# M8650D.net
KiCad netlist of a schematic drawn in EAGLE
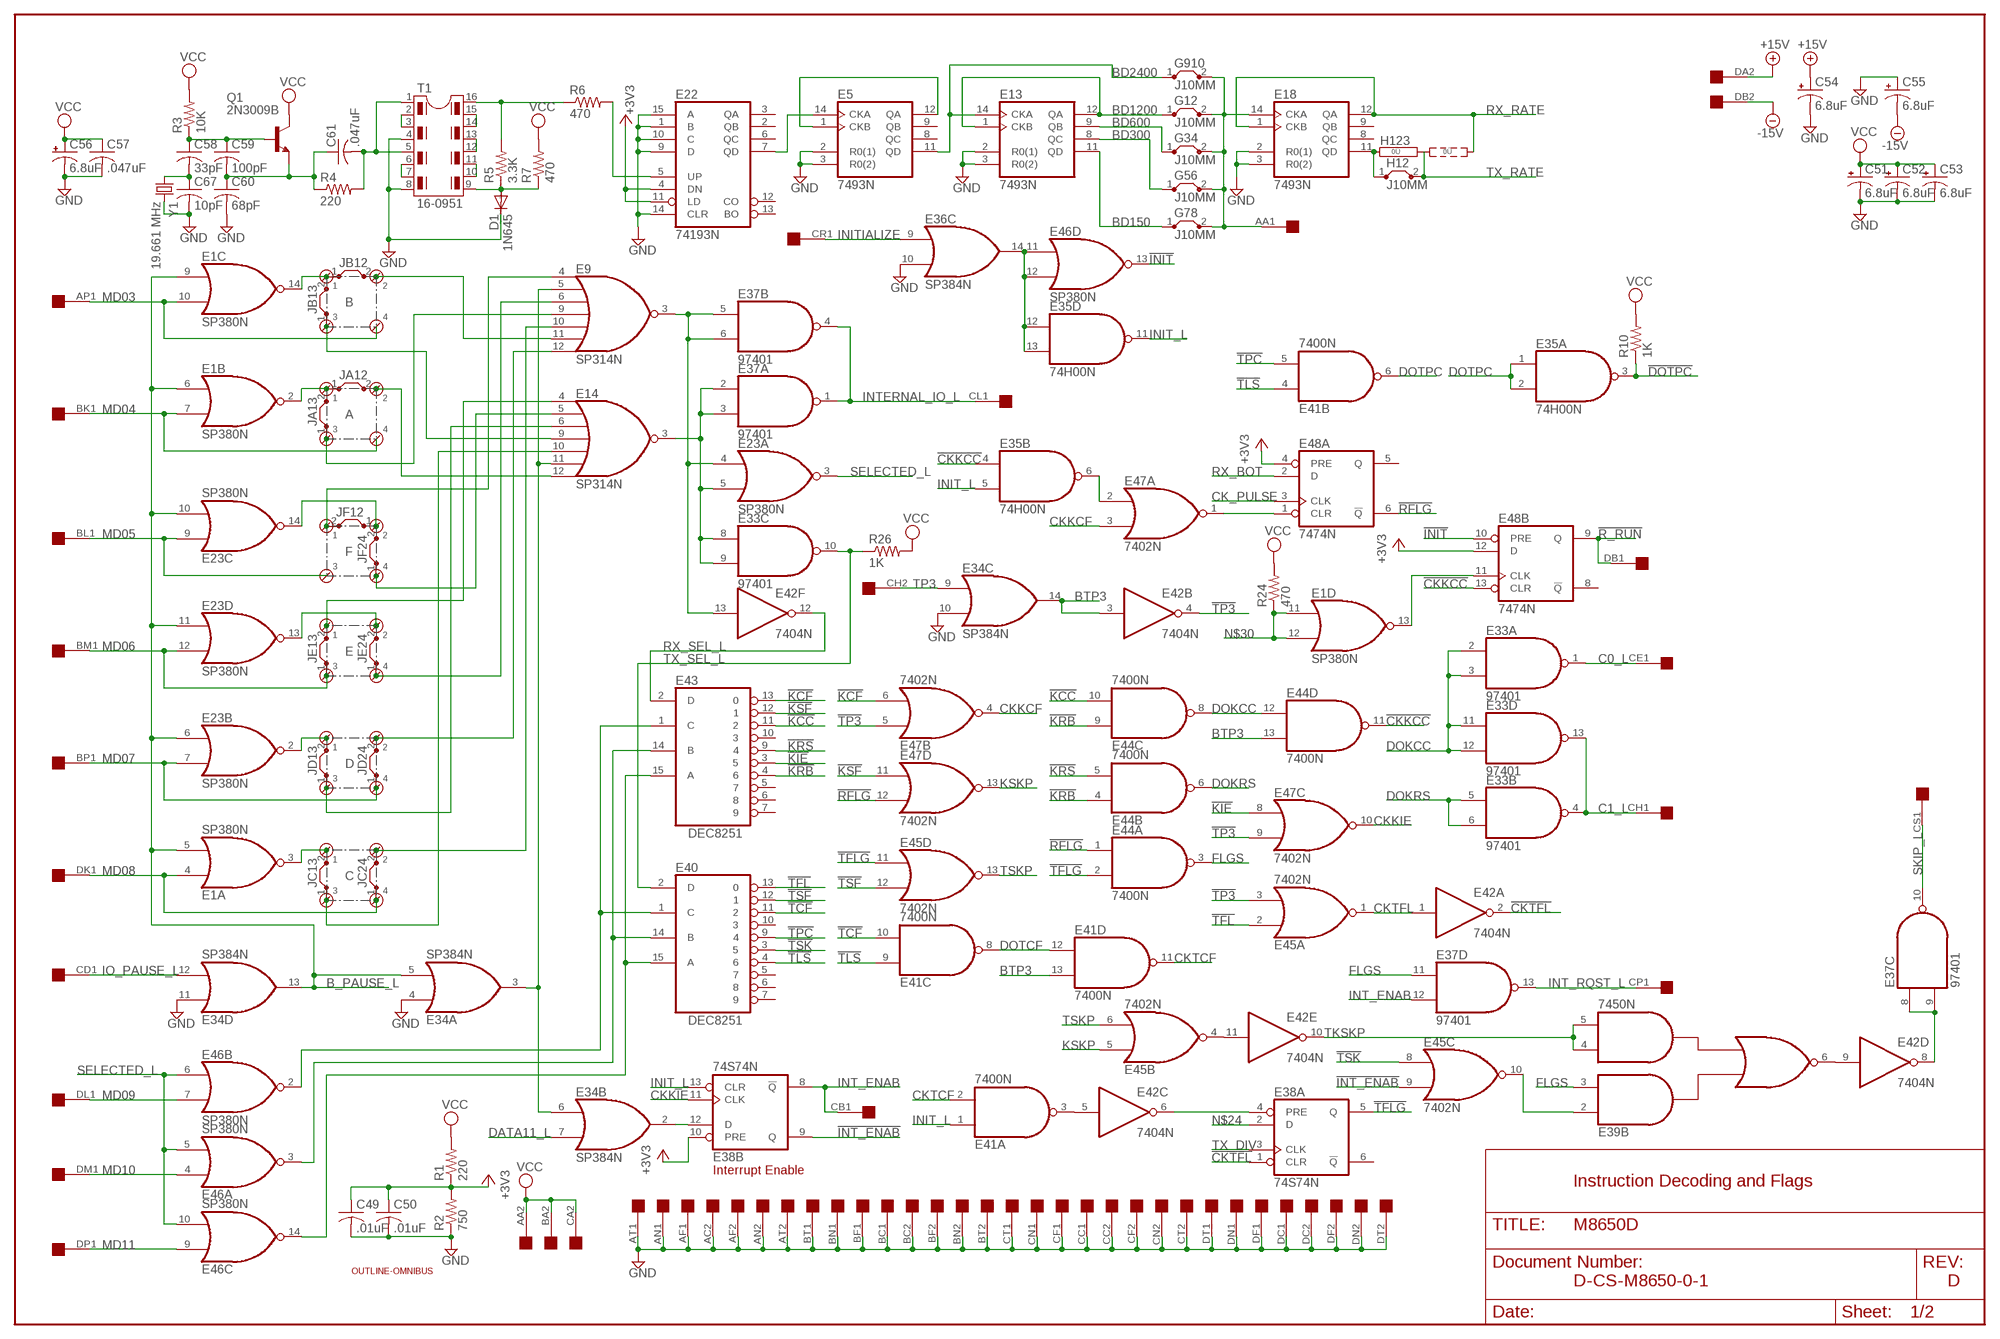
[diagram p0: schematic, sheet 1]
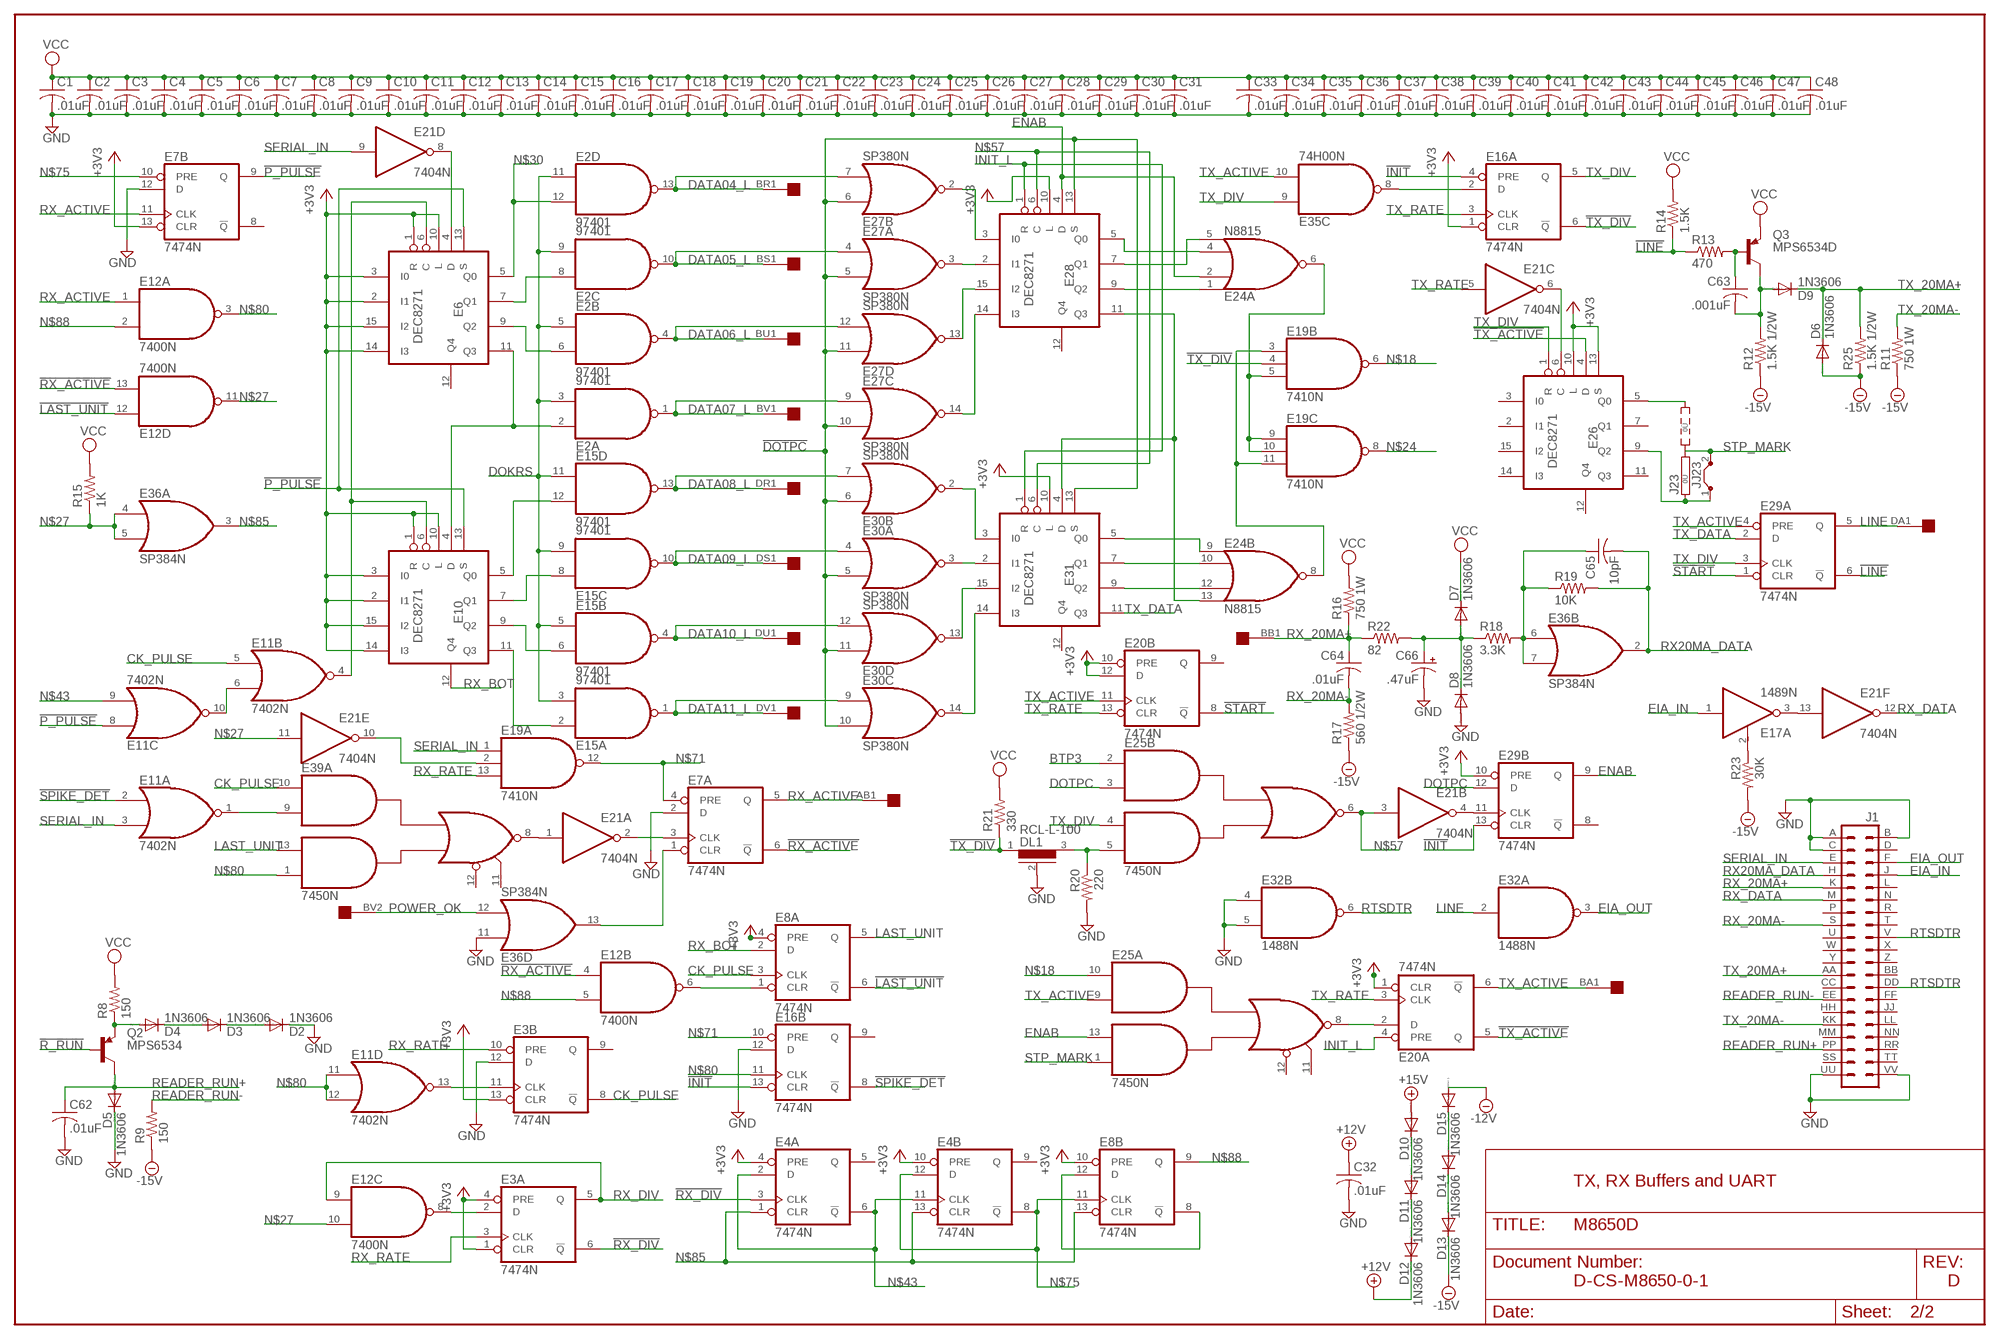
[diagram p1: schematic, sheet 2]

(export (version "E")
  (design (tool "Eeschema 10.0.6"))
  (components
    (comp (ref "A")
      (value "JUMPER4")
      (footprint "eagle-import:JUMPER4")
      (libsource (lib "eagle-import") (part "JUMPER4"))
    )
    (comp (ref "B")
      (value "JUMPER4")
      (footprint "eagle-import:JUMPER4")
      (libsource (lib "eagle-import") (part "JUMPER4"))
    )
    (comp (ref "C")
      (value "JUMPER4")
      (footprint "eagle-import:JUMPER4")
      (libsource (lib "eagle-import") (part "JUMPER4"))
    )
    (comp (ref "C49")
      (value ".01uF")
      (footprint "eagle-import:C050-025X075")
      (libsource (lib "eagle-import") (part "C-US050-025X075"))
    )
    (comp (ref "C50")
      (value ".01uF")
      (footprint "eagle-import:C050-025X075")
      (libsource (lib "eagle-import") (part "C-US050-025X075"))
    )
    (comp (ref "C51")
      (value "6.8uF")
      (footprint "eagle-import:E12-8")
      (libsource (lib "eagle-import") (part "CPOL-USE20-8AXIAL"))
    )
    (comp (ref "C52")
      (value "6.8uF")
      (footprint "eagle-import:E12-8")
      (libsource (lib "eagle-import") (part "CPOL-USE20-8AXIAL"))
    )
    (comp (ref "C53")
      (value "6.8uF")
      (footprint "eagle-import:E12-8")
      (libsource (lib "eagle-import") (part "CPOL-USE20-8AXIAL"))
    )
    (comp (ref "C54")
      (value "6.8uF")
      (footprint "eagle-import:E12-8")
      (libsource (lib "eagle-import") (part "CPOL-USE20-8AXIAL"))
    )
    (comp (ref "C55")
      (value "6.8uF")
      (footprint "eagle-import:E12-8")
      (libsource (lib "eagle-import") (part "CPOL-USE20-8AXIAL"))
    )
    (comp (ref "C56")
      (value "6.8uF")
      (footprint "eagle-import:E12-8")
      (libsource (lib "eagle-import") (part "CPOL-USE20-8AXIAL"))
    )
    (comp (ref "C57")
      (value ".047uF")
      (footprint "eagle-import:C050-025X075")
      (libsource (lib "eagle-import") (part "C-US050-025X075"))
    )
    (comp (ref "C58")
      (value "33pF")
      (footprint "eagle-import:C050-025X075")
      (libsource (lib "eagle-import") (part "C-US050-025X075"))
    )
    (comp (ref "C59")
      (value "100pF")
      (footprint "eagle-import:C050-025X075")
      (libsource (lib "eagle-import") (part "C-US050-025X075"))
    )
    (comp (ref "C60")
      (value "68pF")
      (footprint "eagle-import:C050-025X075")
      (libsource (lib "eagle-import") (part "C-US050-025X075"))
    )
    (comp (ref "C61")
      (value ".047uF")
      (footprint "eagle-import:C050-025X075")
      (libsource (lib "eagle-import") (part "C-US050-025X075"))
    )
    (comp (ref "C67")
      (value "10pF")
      (footprint "eagle-import:C050-025X075")
      (libsource (lib "eagle-import") (part "C-US050-025X075"))
    )
    (comp (ref "D")
      (value "JUMPER4")
      (footprint "eagle-import:JUMPER4")
      (libsource (lib "eagle-import") (part "JUMPER4"))
    )
    (comp (ref "D1")
      (value "1N645")
      (footprint "eagle-import:DO35-10")
      (libsource (lib "eagle-import") (part "DIODE-DO35-10"))
    )
    (comp (ref "E")
      (value "JUMPER4")
      (footprint "eagle-import:JUMPER4")
      (libsource (lib "eagle-import") (part "JUMPER4"))
    )
    (comp (ref "E1")
      (value "SP380N")
      (footprint "eagle-import:DIL14")
      (libsource (lib "eagle-import") (part "SP380N"))
    )
    (comp (ref "E5")
      (value "7493N")
      (footprint "eagle-import:DIL14")
      (libsource (lib "eagle-import") (part "7493NLS"))
    )
    (comp (ref "E9")
      (value "SP314N")
      (footprint "eagle-import:DIL14")
      (libsource (lib "eagle-import") (part "SP314N"))
    )
    (comp (ref "E13")
      (value "7493N")
      (footprint "eagle-import:DIL14")
      (libsource (lib "eagle-import") (part "7493NLS"))
    )
    (comp (ref "E14")
      (value "SP314N")
      (footprint "eagle-import:DIL14")
      (libsource (lib "eagle-import") (part "SP314N"))
    )
    (comp (ref "E18")
      (value "7493N")
      (footprint "eagle-import:DIL14")
      (libsource (lib "eagle-import") (part "7493NLS"))
    )
    (comp (ref "E22")
      (value "74193N")
      (footprint "eagle-import:DIL16")
      (libsource (lib "eagle-import") (part "74193N"))
    )
    (comp (ref "E23")
      (value "SP380N")
      (footprint "eagle-import:DIL14")
      (libsource (lib "eagle-import") (part "SP380N"))
    )
    (comp (ref "E33")
      (value "97401")
      (footprint "eagle-import:DIL14")
      (libsource (lib "eagle-import") (part "7401NLS"))
    )
    (comp (ref "E34")
      (value "SP384N")
      (footprint "eagle-import:DIL14")
      (libsource (lib "eagle-import") (part "SP384N"))
    )
    (comp (ref "E35")
      (value "74H00N")
      (footprint "eagle-import:DIL14")
      (libsource (lib "eagle-import") (part "7400N"))
    )
    (comp (ref "E36")
      (value "SP384N")
      (footprint "eagle-import:DIL14")
      (libsource (lib "eagle-import") (part "SP384N"))
    )
    (comp (ref "E37")
      (value "97401")
      (footprint "eagle-import:DIL14")
      (libsource (lib "eagle-import") (part "7401NLS"))
    )
    (comp (ref "E38")
      (value "74S74N")
      (footprint "eagle-import:DIL14")
      (libsource (lib "eagle-import") (part "7474NS"))
    )
    (comp (ref "E39")
      (value "7450N")
      (footprint "eagle-import:DIL14")
      (libsource (lib "eagle-import") (part "7450N"))
    )
    (comp (ref "E40")
      (value "DEC8251")
      (footprint "eagle-import:DIL16")
      (libsource (lib "eagle-import") (part "DEC8251"))
    )
    (comp (ref "E41")
      (value "7400N")
      (footprint "eagle-import:DIL14")
      (libsource (lib "eagle-import") (part "7400N"))
    )
    (comp (ref "E42")
      (value "7404N")
      (footprint "eagle-import:DIL14")
      (libsource (lib "eagle-import") (part "7404N"))
    )
    (comp (ref "E43")
      (value "DEC8251")
      (footprint "eagle-import:DIL16")
      (libsource (lib "eagle-import") (part "DEC8251"))
    )
    (comp (ref "E44")
      (value "7400N")
      (footprint "eagle-import:DIL14")
      (libsource (lib "eagle-import") (part "7400N"))
    )
    (comp (ref "E45")
      (value "7402N")
      (footprint "eagle-import:DIL14")
      (libsource (lib "eagle-import") (part "7402N"))
    )
    (comp (ref "E46")
      (value "SP380N")
      (footprint "eagle-import:DIL14")
      (libsource (lib "eagle-import") (part "SP380N"))
    )
    (comp (ref "E47")
      (value "7402N")
      (footprint "eagle-import:DIL14")
      (libsource (lib "eagle-import") (part "7402N"))
    )
    (comp (ref "E48")
      (value "7474N")
      (footprint "eagle-import:DIL14")
      (libsource (lib "eagle-import") (part "7474NS"))
    )
    (comp (ref "F")
      (value "JUMPER4")
      (footprint "eagle-import:JUMPER4")
      (libsource (lib "eagle-import") (part "JUMPER4"))
    )
    (comp (ref "G12")
      (value "J10MM")
      (footprint "eagle-import:10")
      (libsource (lib "eagle-import") (part "J10MM"))
    )
    (comp (ref "G34")
      (value "J10MM")
      (footprint "eagle-import:10")
      (libsource (lib "eagle-import") (part "J10MM"))
    )
    (comp (ref "G56")
      (value "J10MM")
      (footprint "eagle-import:10")
      (libsource (lib "eagle-import") (part "J10MM"))
    )
    (comp (ref "G78")
      (value "J10MM")
      (footprint "eagle-import:10")
      (libsource (lib "eagle-import") (part "J10MM"))
    )
    (comp (ref "G910")
      (value "J10MM")
      (footprint "eagle-import:10")
      (libsource (lib "eagle-import") (part "J10MM"))
    )
    (comp (ref "H12")
      (value "J10MM")
      (footprint "eagle-import:10")
      (libsource (lib "eagle-import") (part "J10MM"))
    )
    (comp (ref "H123")
      (value "0R2")
      (footprint "eagle-import:0R2_10")
      (libsource (lib "eagle-import") (part "0R2"))
    )
    (comp (ref "JA12")
      (value "J10MM")
      (footprint "eagle-import:10")
      (libsource (lib "eagle-import") (part "J10MM"))
    )
    (comp (ref "JA13")
      (value "J10MM")
      (footprint "eagle-import:10")
      (libsource (lib "eagle-import") (part "J10MM"))
    )
    (comp (ref "JB12")
      (value "J10MM")
      (footprint "eagle-import:10")
      (libsource (lib "eagle-import") (part "J10MM"))
    )
    (comp (ref "JB13")
      (value "J10MM")
      (footprint "eagle-import:10")
      (libsource (lib "eagle-import") (part "J10MM"))
    )
    (comp (ref "JC13")
      (value "J10MM")
      (footprint "eagle-import:10")
      (libsource (lib "eagle-import") (part "J10MM"))
    )
    (comp (ref "JC24")
      (value "J10MM")
      (footprint "eagle-import:10")
      (libsource (lib "eagle-import") (part "J10MM"))
    )
    (comp (ref "JD13")
      (value "J10MM")
      (footprint "eagle-import:10")
      (libsource (lib "eagle-import") (part "J10MM"))
    )
    (comp (ref "JD24")
      (value "J10MM")
      (footprint "eagle-import:10")
      (libsource (lib "eagle-import") (part "J10MM"))
    )
    (comp (ref "JE13")
      (value "J10MM")
      (footprint "eagle-import:10")
      (libsource (lib "eagle-import") (part "J10MM"))
    )
    (comp (ref "JE24")
      (value "J10MM")
      (footprint "eagle-import:10")
      (libsource (lib "eagle-import") (part "J10MM"))
    )
    (comp (ref "JF12")
      (value "J10MM")
      (footprint "eagle-import:10")
      (libsource (lib "eagle-import") (part "J10MM"))
    )
    (comp (ref "JF24")
      (value "J10MM")
      (footprint "eagle-import:10")
      (libsource (lib "eagle-import") (part "J10MM"))
    )
    (comp (ref "Q1")
      (value "2N3009B")
      (footprint "eagle-import:TO5")
      (libsource (lib "eagle-import") (part "-NPN-TO5"))
    )
    (comp (ref "R1")
      (value "220")
      (footprint "eagle-import:0207_10")
      (libsource (lib "eagle-import") (part "R-US_0207/10"))
    )
    (comp (ref "R2")
      (value "750")
      (footprint "eagle-import:0207_10")
      (libsource (lib "eagle-import") (part "R-US_0207/10"))
    )
    (comp (ref "R3")
      (value "10K")
      (footprint "eagle-import:0207_10")
      (libsource (lib "eagle-import") (part "R-US_0207/10"))
    )
    (comp (ref "R4")
      (value "220")
      (footprint "eagle-import:0207_10")
      (libsource (lib "eagle-import") (part "R-US_0207/10"))
    )
    (comp (ref "R5")
      (value "3.3K")
      (footprint "eagle-import:0207_10")
      (libsource (lib "eagle-import") (part "R-US_0207/10"))
    )
    (comp (ref "R6")
      (value "470")
      (footprint "eagle-import:0207_10")
      (libsource (lib "eagle-import") (part "R-US_0207/10"))
    )
    (comp (ref "R7")
      (value "470")
      (footprint "eagle-import:0207_10")
      (libsource (lib "eagle-import") (part "R-US_0207/10"))
    )
    (comp (ref "R10")
      (value "1K")
      (footprint "eagle-import:0207_10")
      (libsource (lib "eagle-import") (part "R-US_0207/10"))
    )
    (comp (ref "R24")
      (value "470")
      (footprint "eagle-import:0207_10")
      (libsource (lib "eagle-import") (part "R-US_0207/10"))
    )
    (comp (ref "R26")
      (value "1K")
      (footprint "eagle-import:0207_10")
      (libsource (lib "eagle-import") (part "R-US_0207/10"))
    )
    (comp (ref "T1")
      (value "16-0951")
      (footprint "eagle-import:DIL16")
      (libsource (lib "eagle-import") (part "DIL16"))
    )
    (comp (ref "U$1")
      (value "OUTLINE-OMNIBUS")
      (footprint "eagle-import:OMNIBUS")
      (libsource (lib "eagle-import") (part "OUTLINE-OMNIBUS"))
    )
    (comp (ref "U$2")
      (value "QUAD")
      (footprint "eagle-import:EDGE-CON8")
      (libsource (lib "eagle-import") (part "QUAD"))
    )
    (comp (ref "Y1")
      (value "19.661 MHz")
      (footprint "eagle-import:HC49TL-H")
      (libsource (lib "eagle-import") (part "CRYSTALHC49TL-H"))
    )
    (comp (ref "C1")
      (value ".01uF")
      (footprint "eagle-import:C050-025X075")
      (libsource (lib "eagle-import") (part "C-US050-025X075"))
    )
    (comp (ref "C2")
      (value ".01uF")
      (footprint "eagle-import:C050-025X075")
      (libsource (lib "eagle-import") (part "C-US050-025X075"))
    )
    (comp (ref "C3")
      (value ".01uF")
      (footprint "eagle-import:C050-025X075")
      (libsource (lib "eagle-import") (part "C-US050-025X075"))
    )
    (comp (ref "C4")
      (value ".01uF")
      (footprint "eagle-import:C050-025X075")
      (libsource (lib "eagle-import") (part "C-US050-025X075"))
    )
    (comp (ref "C5")
      (value ".01uF")
      (footprint "eagle-import:C050-025X075")
      (libsource (lib "eagle-import") (part "C-US050-025X075"))
    )
    (comp (ref "C6")
      (value ".01uF")
      (footprint "eagle-import:C050-025X075")
      (libsource (lib "eagle-import") (part "C-US050-025X075"))
    )
    (comp (ref "C7")
      (value ".01uF")
      (footprint "eagle-import:C050-025X075")
      (libsource (lib "eagle-import") (part "C-US050-025X075"))
    )
    (comp (ref "C8")
      (value ".01uF")
      (footprint "eagle-import:C050-025X075")
      (libsource (lib "eagle-import") (part "C-US050-025X075"))
    )
    (comp (ref "C9")
      (value ".01uF")
      (footprint "eagle-import:C050-025X075")
      (libsource (lib "eagle-import") (part "C-US050-025X075"))
    )
    (comp (ref "C10")
      (value ".01uF")
      (footprint "eagle-import:C050-025X075")
      (libsource (lib "eagle-import") (part "C-US050-025X075"))
    )
    (comp (ref "C11")
      (value ".01uF")
      (footprint "eagle-import:C050-025X075")
      (libsource (lib "eagle-import") (part "C-US050-025X075"))
    )
    (comp (ref "C12")
      (value ".01uF")
      (footprint "eagle-import:C050-025X075")
      (libsource (lib "eagle-import") (part "C-US050-025X075"))
    )
    (comp (ref "C13")
      (value ".01uF")
      (footprint "eagle-import:C050-025X075")
      (libsource (lib "eagle-import") (part "C-US050-025X075"))
    )
    (comp (ref "C14")
      (value ".01uF")
      (footprint "eagle-import:C050-025X075")
      (libsource (lib "eagle-import") (part "C-US050-025X075"))
    )
    (comp (ref "C15")
      (value ".01uF")
      (footprint "eagle-import:C050-025X075")
      (libsource (lib "eagle-import") (part "C-US050-025X075"))
    )
    (comp (ref "C16")
      (value ".01uF")
      (footprint "eagle-import:C050-025X075")
      (libsource (lib "eagle-import") (part "C-US050-025X075"))
    )
    (comp (ref "C17")
      (value ".01uF")
      (footprint "eagle-import:C050-025X075")
      (libsource (lib "eagle-import") (part "C-US050-025X075"))
    )
    (comp (ref "C18")
      (value ".01uF")
      (footprint "eagle-import:C050-025X075")
      (libsource (lib "eagle-import") (part "C-US050-025X075"))
    )
    (comp (ref "C19")
      (value ".01uF")
      (footprint "eagle-import:C050-025X075")
      (libsource (lib "eagle-import") (part "C-US050-025X075"))
    )
    (comp (ref "C20")
      (value ".01uF")
      (footprint "eagle-import:C050-025X075")
      (libsource (lib "eagle-import") (part "C-US050-025X075"))
    )
    (comp (ref "C21")
      (value ".01uF")
      (footprint "eagle-import:C050-025X075")
      (libsource (lib "eagle-import") (part "C-US050-025X075"))
    )
    (comp (ref "C22")
      (value ".01uF")
      (footprint "eagle-import:C050-025X075")
      (libsource (lib "eagle-import") (part "C-US050-025X075"))
    )
    (comp (ref "C23")
      (value ".01uF")
      (footprint "eagle-import:C050-025X075")
      (libsource (lib "eagle-import") (part "C-US050-025X075"))
    )
    (comp (ref "C24")
      (value ".01uF")
      (footprint "eagle-import:C050-025X075")
      (libsource (lib "eagle-import") (part "C-US050-025X075"))
    )
    (comp (ref "C25")
      (value ".01uF")
      (footprint "eagle-import:C050-025X075")
      (libsource (lib "eagle-import") (part "C-US050-025X075"))
    )
    (comp (ref "C26")
      (value ".01uF")
      (footprint "eagle-import:C050-025X075")
      (libsource (lib "eagle-import") (part "C-US050-025X075"))
    )
    (comp (ref "C27")
      (value ".01uF")
      (footprint "eagle-import:C050-025X075")
      (libsource (lib "eagle-import") (part "C-US050-025X075"))
    )
    (comp (ref "C28")
      (value ".01uF")
      (footprint "eagle-import:C050-025X075")
      (libsource (lib "eagle-import") (part "C-US050-025X075"))
    )
    (comp (ref "C29")
      (value ".01uF")
      (footprint "eagle-import:C050-025X075")
      (libsource (lib "eagle-import") (part "C-US050-025X075"))
    )
    (comp (ref "C30")
      (value ".01uF")
      (footprint "eagle-import:C050-025X075")
      (libsource (lib "eagle-import") (part "C-US050-025X075"))
    )
    (comp (ref "C31")
      (value ".01uF")
      (footprint "eagle-import:C050-025X075")
      (libsource (lib "eagle-import") (part "C-US050-025X075"))
    )
    (comp (ref "C32")
      (value ".01uF")
      (footprint "eagle-import:C050-025X075")
      (libsource (lib "eagle-import") (part "C-US050-025X075"))
    )
    (comp (ref "C33")
      (value ".01uF")
      (footprint "eagle-import:C050-025X075")
      (libsource (lib "eagle-import") (part "C-US050-025X075"))
    )
    (comp (ref "C34")
      (value ".01uF")
      (footprint "eagle-import:C050-025X075")
      (libsource (lib "eagle-import") (part "C-US050-025X075"))
    )
    (comp (ref "C35")
      (value ".01uF")
      (footprint "eagle-import:C050-025X075")
      (libsource (lib "eagle-import") (part "C-US050-025X075"))
    )
    (comp (ref "C36")
      (value ".01uF")
      (footprint "eagle-import:C050-025X075")
      (libsource (lib "eagle-import") (part "C-US050-025X075"))
    )
    (comp (ref "C37")
      (value ".01uF")
      (footprint "eagle-import:C050-025X075")
      (libsource (lib "eagle-import") (part "C-US050-025X075"))
    )
    (comp (ref "C38")
      (value ".01uF")
      (footprint "eagle-import:C050-025X075")
      (libsource (lib "eagle-import") (part "C-US050-025X075"))
    )
    (comp (ref "C39")
      (value ".01uF")
      (footprint "eagle-import:C050-025X075")
      (libsource (lib "eagle-import") (part "C-US050-025X075"))
    )
    (comp (ref "C40")
      (value ".01uF")
      (footprint "eagle-import:C050-025X075")
      (libsource (lib "eagle-import") (part "C-US050-025X075"))
    )
    (comp (ref "C41")
      (value ".01uF")
      (footprint "eagle-import:C050-025X075")
      (libsource (lib "eagle-import") (part "C-US050-025X075"))
    )
    (comp (ref "C42")
      (value ".01uF")
      (footprint "eagle-import:C050-025X075")
      (libsource (lib "eagle-import") (part "C-US050-025X075"))
    )
    (comp (ref "C43")
      (value ".01uF")
      (footprint "eagle-import:C050-025X075")
      (libsource (lib "eagle-import") (part "C-US050-025X075"))
    )
    (comp (ref "C44")
      (value ".01uF")
      (footprint "eagle-import:C050-025X075")
      (libsource (lib "eagle-import") (part "C-US050-025X075"))
    )
    (comp (ref "C45")
      (value ".01uF")
      (footprint "eagle-import:C050-025X075")
      (libsource (lib "eagle-import") (part "C-US050-025X075"))
    )
    (comp (ref "C46")
      (value ".01uF")
      (footprint "eagle-import:C050-025X075")
      (libsource (lib "eagle-import") (part "C-US050-025X075"))
    )
    (comp (ref "C47")
      (value ".01uF")
      (footprint "eagle-import:C050-025X075")
      (libsource (lib "eagle-import") (part "C-US050-025X075"))
    )
    (comp (ref "C48")
      (value ".01uF")
      (footprint "eagle-import:C050-025X075")
      (libsource (lib "eagle-import") (part "C-US050-025X075"))
    )
    (comp (ref "C62")
      (value ".01uF")
      (footprint "eagle-import:C050-025X075")
      (libsource (lib "eagle-import") (part "C-US050-025X075"))
    )
    (comp (ref "C63")
      (value ".001uF")
      (footprint "eagle-import:C050-025X075")
      (libsource (lib "eagle-import") (part "C-US050-025X075"))
    )
    (comp (ref "C64")
      (value ".01uF")
      (footprint "eagle-import:C050-025X075")
      (libsource (lib "eagle-import") (part "C-US050-025X075"))
    )
    (comp (ref "C65")
      (value "10pF")
      (footprint "eagle-import:C050-025X075")
      (libsource (lib "eagle-import") (part "C-US050-025X075"))
    )
    (comp (ref "C66")
      (value ".47uF")
      (footprint "eagle-import:E15-5")
      (libsource (lib "eagle-import") (part "CPOL-USE15-5AXIAL"))
    )
    (comp (ref "D2")
      (value "1N3606")
      (footprint "eagle-import:DO35-10")
      (libsource (lib "eagle-import") (part "DIODE-DO35-10"))
    )
    (comp (ref "D3")
      (value "1N3606")
      (footprint "eagle-import:DO35-10")
      (libsource (lib "eagle-import") (part "DIODE-DO35-10"))
    )
    (comp (ref "D4")
      (value "1N3606")
      (footprint "eagle-import:DO35-10")
      (libsource (lib "eagle-import") (part "DIODE-DO35-10"))
    )
    (comp (ref "D5")
      (value "1N3606")
      (footprint "eagle-import:DO35-10")
      (libsource (lib "eagle-import") (part "DIODE-DO35-10"))
    )
    (comp (ref "D6")
      (value "1N3606")
      (footprint "eagle-import:DO35-10")
      (libsource (lib "eagle-import") (part "DIODE-DO35-10"))
    )
    (comp (ref "D7")
      (value "1N3606")
      (footprint "eagle-import:DO35-10")
      (libsource (lib "eagle-import") (part "DIODE-DO35-10"))
    )
    (comp (ref "D8")
      (value "1N3606")
      (footprint "eagle-import:DO35-10")
      (libsource (lib "eagle-import") (part "DIODE-DO35-10"))
    )
    (comp (ref "D9")
      (value "1N3606")
      (footprint "eagle-import:DO35-10")
      (libsource (lib "eagle-import") (part "DIODE-DO35-10"))
    )
    (comp (ref "D10")
      (value "1N3606")
      (footprint "eagle-import:DO35-10")
      (libsource (lib "eagle-import") (part "DIODE-DO35-10"))
    )
    (comp (ref "D11")
      (value "1N3606")
      (footprint "eagle-import:DO35-10")
      (libsource (lib "eagle-import") (part "DIODE-DO35-10"))
    )
    (comp (ref "D12")
      (value "1N3606")
      (footprint "eagle-import:DO35-10")
      (libsource (lib "eagle-import") (part "DIODE-DO35-10"))
    )
    (comp (ref "D13")
      (value "1N3606")
      (footprint "eagle-import:DO35-10")
      (libsource (lib "eagle-import") (part "DIODE-DO35-10"))
    )
    (comp (ref "D14")
      (value "1N3606")
      (footprint "eagle-import:DO35-10")
      (libsource (lib "eagle-import") (part "DIODE-DO35-10"))
    )
    (comp (ref "D15")
      (value "1N3606")
      (footprint "eagle-import:DO35-10")
      (libsource (lib "eagle-import") (part "DIODE-DO35-10"))
    )
    (comp (ref "DL1")
      (value "RCL-L-100")
      (footprint "eagle-import:RCL-L-00-05")
      (libsource (lib "eagle-import") (part "RCL-L-00-05"))
    )
    (comp (ref "E2")
      (value "97401")
      (footprint "eagle-import:DIL14")
      (libsource (lib "eagle-import") (part "7401NLS"))
    )
    (comp (ref "E3")
      (value "7474N")
      (footprint "eagle-import:DIL14")
      (libsource (lib "eagle-import") (part "7474NS"))
    )
    (comp (ref "E4")
      (value "7474N")
      (footprint "eagle-import:DIL14")
      (libsource (lib "eagle-import") (part "7474NS"))
    )
    (comp (ref "E6")
      (value "DEC8271")
      (footprint "eagle-import:DIL16")
      (libsource (lib "eagle-import") (part "DEC8271"))
    )
    (comp (ref "E7")
      (value "7474N")
      (footprint "eagle-import:DIL14")
      (libsource (lib "eagle-import") (part "7474NS"))
    )
    (comp (ref "E8")
      (value "7474N")
      (footprint "eagle-import:DIL14")
      (libsource (lib "eagle-import") (part "7474NS"))
    )
    (comp (ref "E10")
      (value "DEC8271")
      (footprint "eagle-import:DIL16")
      (libsource (lib "eagle-import") (part "DEC8271"))
    )
    (comp (ref "E11")
      (value "7402N")
      (footprint "eagle-import:DIL14")
      (libsource (lib "eagle-import") (part "7402N"))
    )
    (comp (ref "E12")
      (value "7400N")
      (footprint "eagle-import:DIL14")
      (libsource (lib "eagle-import") (part "7400N"))
    )
    (comp (ref "E15")
      (value "97401")
      (footprint "eagle-import:DIL14")
      (libsource (lib "eagle-import") (part "7401NLS"))
    )
    (comp (ref "E16")
      (value "7474N")
      (footprint "eagle-import:DIL14")
      (libsource (lib "eagle-import") (part "7474NS"))
    )
    (comp (ref "E17")
      (value "1489N")
      (footprint "eagle-import:DIL14")
      (libsource (lib "eagle-import") (part "1489N"))
    )
    (comp (ref "E19")
      (value "7410N")
      (footprint "eagle-import:DIL14")
      (libsource (lib "eagle-import") (part "7410N"))
    )
    (comp (ref "E20")
      (value "7474N")
      (footprint "eagle-import:DIL14")
      (libsource (lib "eagle-import") (part "7474NS"))
    )
    (comp (ref "E21")
      (value "7404N")
      (footprint "eagle-import:DIL14")
      (libsource (lib "eagle-import") (part "7404N"))
    )
    (comp (ref "E24")
      (value "N8815")
      (footprint "eagle-import:DIL14")
      (libsource (lib "eagle-import") (part "N8815"))
    )
    (comp (ref "E25")
      (value "7450N")
      (footprint "eagle-import:DIL14")
      (libsource (lib "eagle-import") (part "7450N"))
    )
    (comp (ref "E26")
      (value "DEC8271")
      (footprint "eagle-import:DIL16")
      (libsource (lib "eagle-import") (part "DEC8271"))
    )
    (comp (ref "E27")
      (value "SP380N")
      (footprint "eagle-import:DIL14")
      (libsource (lib "eagle-import") (part "SP380N"))
    )
    (comp (ref "E28")
      (value "DEC8271")
      (footprint "eagle-import:DIL16")
      (libsource (lib "eagle-import") (part "DEC8271"))
    )
    (comp (ref "E29")
      (value "7474N")
      (footprint "eagle-import:DIL14")
      (libsource (lib "eagle-import") (part "7474NS"))
    )
    (comp (ref "E30")
      (value "SP380N")
      (footprint "eagle-import:DIL14")
      (libsource (lib "eagle-import") (part "SP380N"))
    )
    (comp (ref "E31")
      (value "DEC8271")
      (footprint "eagle-import:DIL16")
      (libsource (lib "eagle-import") (part "DEC8271"))
    )
    (comp (ref "E32")
      (value "1488N")
      (footprint "eagle-import:DIL14")
      (libsource (lib "eagle-import") (part "1488N"))
    )
    (comp (ref "J1")
      (value "DEC40PINH")
      (footprint "eagle-import:DEC40PINH")
      (libsource (lib "eagle-import") (part "DEC40PINH"))
    )
    (comp (ref "J23")
      (value "0R2")
      (footprint "eagle-import:0R2_10")
      (libsource (lib "eagle-import") (part "0R2"))
    )
    (comp (ref "JJ23")
      (value "J10MM")
      (footprint "eagle-import:10")
      (libsource (lib "eagle-import") (part "J10MM"))
    )
    (comp (ref "Q2")
      (value "MPS6534")
      (footprint "eagle-import:TO5")
      (libsource (lib "eagle-import") (part "-PNP-TO5"))
    )
    (comp (ref "Q3")
      (value "MPS6534D")
      (footprint "eagle-import:TO5")
      (libsource (lib "eagle-import") (part "-PNP-TO5"))
    )
    (comp (ref "R8")
      (value "150")
      (footprint "eagle-import:0207_10")
      (libsource (lib "eagle-import") (part "R-US_0207/10"))
    )
    (comp (ref "R9")
      (value "150")
      (footprint "eagle-import:0207_10")
      (libsource (lib "eagle-import") (part "R-US_0207/10"))
    )
    (comp (ref "R11")
      (value "750 1W")
      (footprint "eagle-import:0617_17")
      (libsource (lib "eagle-import") (part "R-US_0617/17"))
    )
    (comp (ref "R12")
      (value "1.5K 1/2W")
      (footprint "eagle-import:0411_15")
      (libsource (lib "eagle-import") (part "R-US_0411/15"))
    )
    (comp (ref "R13")
      (value "470")
      (footprint "eagle-import:0207_10")
      (libsource (lib "eagle-import") (part "R-US_0207/10"))
    )
    (comp (ref "R14")
      (value "1.5K")
      (footprint "eagle-import:0207_10")
      (libsource (lib "eagle-import") (part "R-US_0207/10"))
    )
    (comp (ref "R15")
      (value "1K")
      (footprint "eagle-import:0207_10")
      (libsource (lib "eagle-import") (part "R-US_0207/10"))
    )
    (comp (ref "R16")
      (value "750 1W")
      (footprint "eagle-import:0617_17")
      (libsource (lib "eagle-import") (part "R-US_0617/17"))
    )
    (comp (ref "R17")
      (value "560 1/2W")
      (footprint "eagle-import:0411_15")
      (libsource (lib "eagle-import") (part "R-US_0411/15"))
    )
    (comp (ref "R18")
      (value "3.3K")
      (footprint "eagle-import:0207_10")
      (libsource (lib "eagle-import") (part "R-US_0207/10"))
    )
    (comp (ref "R19")
      (value "10K")
      (footprint "eagle-import:0207_10")
      (libsource (lib "eagle-import") (part "R-US_0207/10"))
    )
    (comp (ref "R20")
      (value "220")
      (footprint "eagle-import:0207_10")
      (libsource (lib "eagle-import") (part "R-US_0207/10"))
    )
    (comp (ref "R21")
      (value "330")
      (footprint "eagle-import:0207_10")
      (libsource (lib "eagle-import") (part "R-US_0207/10"))
    )
    (comp (ref "R22")
      (value "82")
      (footprint "eagle-import:0207_10")
      (libsource (lib "eagle-import") (part "R-US_0207/10"))
    )
    (comp (ref "R23")
      (value "30K")
      (footprint "eagle-import:0207_10")
      (libsource (lib "eagle-import") (part "R-US_0207/10"))
    )
    (comp (ref "R25")
      (value "1.5K 1/2W")
      (footprint "eagle-import:0411_15")
      (libsource (lib "eagle-import") (part "R-US_0411/15"))
    )
  )
  (nets
    (net (code "1") (name "+3V3") (class "Default")
      (node (ref "C49") (pin "1") (pinfunction "1_1") (pintype "passive"))
      (node (ref "C50") (pin "1") (pinfunction "1_1") (pintype "passive"))
      (node (ref "E10") (pin "1") (pinfunction "R_1") (pintype "input"))
      (node (ref "E10") (pin "10") (pinfunction "L_10") (pintype "input"))
      (node (ref "E10") (pin "14") (pinfunction "I3_14") (pintype "input"))
      (node (ref "E10") (pin "15") (pinfunction "I2_15") (pintype "input"))
      (node (ref "E10") (pin "2") (pinfunction "I1_2") (pintype "input"))
      (node (ref "E10") (pin "3") (pinfunction "I0_3") (pintype "input"))
      (node (ref "E16") (pin "1") (pinfunction "CLR_1") (pintype "input"))
      (node (ref "E20") (pin "1") (pinfunction "CLR_1") (pintype "input"))
      (node (ref "E20") (pin "10") (pinfunction "PRE_10") (pintype "input"))
      (node (ref "E20") (pin "12") (pinfunction "D_12") (pintype "input"))
      (node (ref "E22") (pin "11") (pinfunction "LD_11") (pintype "input"))
      (node (ref "E22") (pin "4") (pinfunction "DN_4") (pintype "input"))
      (node (ref "E26") (pin "10") (pinfunction "L_10") (pintype "input"))
      (node (ref "E26") (pin "13") (pinfunction "S_13") (pintype "input"))
      (node (ref "E28") (pin "10") (pinfunction "L_10") (pintype "input"))
      (node (ref "E29") (pin "10") (pinfunction "PRE_10") (pintype "input"))
      (node (ref "E3") (pin "1") (pinfunction "CLR_1") (pintype "input"))
      (node (ref "E3") (pin "13") (pinfunction "CLR_13") (pintype "input"))
      (node (ref "E3") (pin "4") (pinfunction "PRE_4") (pintype "input"))
      (node (ref "E31") (pin "10") (pinfunction "L_10") (pintype "input"))
      (node (ref "E38") (pin "10") (pinfunction "PRE_10") (pintype "input"))
      (node (ref "E4") (pin "10") (pinfunction "PRE_10") (pintype "input"))
      (node (ref "E4") (pin "4") (pinfunction "PRE_4") (pintype "input"))
      (node (ref "E48") (pin "12") (pinfunction "D_12") (pintype "input"))
      (node (ref "E48") (pin "4") (pinfunction "PRE_4") (pintype "input"))
      (node (ref "E6") (pin "1") (pinfunction "R_1") (pintype "input"))
      (node (ref "E6") (pin "10") (pinfunction "L_10") (pintype "input"))
      (node (ref "E6") (pin "14") (pinfunction "I3_14") (pintype "input"))
      (node (ref "E6") (pin "15") (pinfunction "I2_15") (pintype "input"))
      (node (ref "E6") (pin "2") (pinfunction "I1_2") (pintype "input"))
      (node (ref "E6") (pin "3") (pinfunction "I0_3") (pintype "input"))
      (node (ref "E7") (pin "13") (pinfunction "CLR_13") (pintype "input"))
      (node (ref "E8") (pin "10") (pinfunction "PRE_10") (pintype "input"))
      (node (ref "E8") (pin "4") (pinfunction "PRE_4") (pintype "input"))
      (node (ref "R1") (pin "1") (pinfunction "1_1") (pintype "passive"))
      (node (ref "R2") (pin "2") (pinfunction "2_2") (pintype "passive"))
    )
    (net (code "2") (name "+12V") (class "Default")
      (node (ref "C32") (pin "1") (pinfunction "1_1") (pintype "passive"))
      (node (ref "D12") (pin "C") (pinfunction "C_C") (pintype "passive"))
    )
    (net (code "3") (name "+15V") (class "Default")
      (node (ref "C54") (pin "+") (pinfunction "+_+") (pintype "passive"))
      (node (ref "D10") (pin "A") (pinfunction "A_A") (pintype "passive"))
      (node (ref "U$2") (pin "DA2") (pinfunction "1_DA2") (pintype "bidirectional"))
    )
    (net (code "4") (name "-12V") (class "Default")
      (node (ref "D15") (pin "A") (pinfunction "A_A") (pintype "passive"))
    )
    (net (code "5") (name "-15V") (class "Default")
      (node (ref "C55") (pin "-") (pinfunction "-_-") (pintype "passive"))
      (node (ref "D13") (pin "C") (pinfunction "C_C") (pintype "passive"))
      (node (ref "D6") (pin "A") (pinfunction "A_A") (pintype "passive"))
      (node (ref "R11") (pin "1") (pinfunction "1_1") (pintype "passive"))
      (node (ref "R12") (pin "1") (pinfunction "1_1") (pintype "passive"))
      (node (ref "R17") (pin "1") (pinfunction "1_1") (pintype "passive"))
      (node (ref "R23") (pin "2") (pinfunction "2_2") (pintype "passive"))
      (node (ref "R25") (pin "1") (pinfunction "1_1") (pintype "passive"))
      (node (ref "R9") (pin "1") (pinfunction "1_1") (pintype "passive"))
      (node (ref "U$2") (pin "DB2") (pinfunction "1_DB2") (pintype "bidirectional"))
    )
    (net (code "6") (name "BD150") (class "Default")
      (node (ref "E13") (pin "11") (pinfunction "QD_11") (pintype "output"))
      (node (ref "G78") (pin "1") (pinfunction "1_1") (pintype "passive"))
    )
    (net (code "7") (name "BD300") (class "Default")
      (node (ref "E13") (pin "8") (pinfunction "QC_8") (pintype "output"))
      (node (ref "G56") (pin "1") (pinfunction "1_1") (pintype "passive"))
    )
    (net (code "8") (name "BD600") (class "Default")
      (node (ref "E13") (pin "9") (pinfunction "QB_9") (pintype "output"))
      (node (ref "G34") (pin "1") (pinfunction "1_1") (pintype "passive"))
    )
    (net (code "9") (name "BD1200") (class "Default")
      (node (ref "E13") (pin "1") (pinfunction "CKB_1") (pintype "input"))
      (node (ref "E13") (pin "12") (pinfunction "QA_12") (pintype "output"))
      (node (ref "G12") (pin "1") (pinfunction "1_1") (pintype "passive"))
    )
    (net (code "10") (name "BD2400") (class "Default")
      (node (ref "E13") (pin "14") (pinfunction "CKA_14") (pintype "input"))
      (node (ref "E5") (pin "11") (pinfunction "QD_11") (pintype "output"))
      (node (ref "G910") (pin "1") (pinfunction "1_1") (pintype "passive"))
    )
    (net (code "11") (name "BTP3") (class "Default")
      (node (ref "E25") (pin "2") (pinfunction "I1_2") (pintype "input"))
      (node (ref "E34") (pin "14") (pinfunction "O_14") (pintype "output"))
      (node (ref "E41") (pin "13") (pinfunction "I1_13") (pintype "input"))
      (node (ref "E42") (pin "3") (pinfunction "I_3") (pintype "input"))
      (node (ref "E44") (pin "13") (pinfunction "I1_13") (pintype "input"))
    )
    (net (code "12") (name "B_PAUSE_L") (class "Default")
      (node (ref "E1") (pin "5") (pinfunction "I1_5") (pintype "input"))
      (node (ref "E1") (pin "6") (pinfunction "I0_6") (pintype "input"))
      (node (ref "E1") (pin "9") (pinfunction "I0_9") (pintype "input"))
      (node (ref "E23") (pin "10") (pinfunction "I1_10") (pintype "input"))
      (node (ref "E23") (pin "11") (pinfunction "I0_11") (pintype "input"))
      (node (ref "E23") (pin "6") (pinfunction "I0_6") (pintype "input"))
      (node (ref "E34") (pin "13") (pinfunction "O_13") (pintype "output"))
      (node (ref "E34") (pin "5") (pinfunction "I1_5") (pintype "input"))
    )
    (net (code "13") (name "C0_L") (class "Default")
      (node (ref "E33") (pin "1") (pinfunction "O_1") (pintype "open_collector"))
      (node (ref "U$2") (pin "CE1") (pinfunction "1_CE1") (pintype "bidirectional"))
    )
    (net (code "14") (name "C1_L") (class "Default")
      (node (ref "E33") (pin "13") (pinfunction "O_13") (pintype "open_collector"))
      (node (ref "E33") (pin "4") (pinfunction "O_4") (pintype "open_collector"))
      (node (ref "U$2") (pin "CH1") (pinfunction "1_CH1") (pintype "bidirectional"))
    )
    (net (code "15") (name "CKKCF") (class "Default")
      (node (ref "E47") (pin "3") (pinfunction "I1_3") (pintype "input"))
      (node (ref "E47") (pin "4") (pinfunction "O_4") (pintype "output"))
    )
    (net (code "16") (name "CKKIE") (class "Default")
      (node (ref "E38") (pin "11") (pinfunction "CLK_11") (pintype "input"))
      (node (ref "E47") (pin "10") (pinfunction "O_10") (pintype "output"))
    )
    (net (code "17") (name "CKTCF") (class "Default")
      (node (ref "E41") (pin "11") (pinfunction "O_11") (pintype "output"))
      (node (ref "E41") (pin "2") (pinfunction "I1_2") (pintype "input"))
    )
    (net (code "18") (name "CKTFL") (class "Default")
      (node (ref "E42") (pin "1") (pinfunction "I_1") (pintype "input"))
      (node (ref "E45") (pin "1") (pinfunction "O_1") (pintype "output"))
    )
    (net (code "19") (name "CK_PULSE") (class "Default")
      (node (ref "E11") (pin "5") (pinfunction "I0_5") (pintype "input"))
      (node (ref "E3") (pin "8") (pinfunction "~{Q}_8") (pintype "output"))
      (node (ref "E39") (pin "10") (pinfunction "I1_10") (pintype "input"))
      (node (ref "E48") (pin "3") (pinfunction "CLK_3") (pintype "input"))
      (node (ref "E8") (pin "3") (pinfunction "CLK_3") (pintype "input"))
    )
    (net (code "20") (name "DATA04_L") (class "Default")
      (node (ref "E2") (pin "13") (pinfunction "O_13") (pintype "open_collector"))
      (node (ref "E27") (pin "7") (pinfunction "I1_7") (pintype "input"))
      (node (ref "U$2") (pin "BR1") (pinfunction "1_BR1") (pintype "bidirectional"))
    )
    (net (code "21") (name "DATA05_L") (class "Default")
      (node (ref "E2") (pin "10") (pinfunction "O_10") (pintype "open_collector"))
      (node (ref "E27") (pin "4") (pinfunction "I0_4") (pintype "input"))
      (node (ref "U$2") (pin "BS1") (pinfunction "1_BS1") (pintype "bidirectional"))
    )
    (net (code "22") (name "DATA06_L") (class "Default")
      (node (ref "E2") (pin "4") (pinfunction "O_4") (pintype "open_collector"))
      (node (ref "E27") (pin "12") (pinfunction "I1_12") (pintype "input"))
      (node (ref "U$2") (pin "BU1") (pinfunction "1_BU1") (pintype "bidirectional"))
    )
    (net (code "23") (name "DATA07_L") (class "Default")
      (node (ref "E2") (pin "1") (pinfunction "O_1") (pintype "open_collector"))
      (node (ref "E27") (pin "9") (pinfunction "I0_9") (pintype "input"))
      (node (ref "U$2") (pin "BV1") (pinfunction "1_BV1") (pintype "bidirectional"))
    )
    (net (code "24") (name "DATA08_L") (class "Default")
      (node (ref "E15") (pin "13") (pinfunction "O_13") (pintype "open_collector"))
      (node (ref "E30") (pin "7") (pinfunction "I1_7") (pintype "input"))
      (node (ref "U$2") (pin "DR1") (pinfunction "1_DR1") (pintype "bidirectional"))
    )
    (net (code "25") (name "DATA09_L") (class "Default")
      (node (ref "E15") (pin "10") (pinfunction "O_10") (pintype "open_collector"))
      (node (ref "E30") (pin "4") (pinfunction "I0_4") (pintype "input"))
      (node (ref "U$2") (pin "DS1") (pinfunction "1_DS1") (pintype "bidirectional"))
    )
    (net (code "26") (name "DATA10_L") (class "Default")
      (node (ref "E15") (pin "4") (pinfunction "O_4") (pintype "open_collector"))
      (node (ref "E30") (pin "12") (pinfunction "I1_12") (pintype "input"))
      (node (ref "U$2") (pin "DU1") (pinfunction "1_DU1") (pintype "bidirectional"))
    )
    (net (code "27") (name "DATA11_L") (class "Default")
      (node (ref "E15") (pin "1") (pinfunction "O_1") (pintype "open_collector"))
      (node (ref "E30") (pin "9") (pinfunction "I0_9") (pintype "input"))
      (node (ref "E34") (pin "7") (pinfunction "I1_7") (pintype "input"))
      (node (ref "U$2") (pin "DV1") (pinfunction "1_DV1") (pintype "bidirectional"))
    )
    (net (code "28") (name "DOKCC") (class "Default")
      (node (ref "E33") (pin "11") (pinfunction "I0_11") (pintype "input"))
      (node (ref "E33") (pin "12") (pinfunction "I1_12") (pintype "input"))
      (node (ref "E33") (pin "2") (pinfunction "I0_2") (pintype "input"))
      (node (ref "E33") (pin "3") (pinfunction "I1_3") (pintype "input"))
      (node (ref "E44") (pin "12") (pinfunction "I0_12") (pintype "input"))
      (node (ref "E44") (pin "8") (pinfunction "O_8") (pintype "output"))
    )
    (net (code "29") (name "DOKRS") (class "Default")
      (node (ref "E15") (pin "11") (pinfunction "I0_11") (pintype "input"))
      (node (ref "E15") (pin "3") (pinfunction "I1_3") (pintype "input"))
      (node (ref "E15") (pin "5") (pinfunction "I0_5") (pintype "input"))
      (node (ref "E15") (pin "9") (pinfunction "I1_9") (pintype "input"))
      (node (ref "E2") (pin "11") (pinfunction "I0_11") (pintype "input"))
      (node (ref "E2") (pin "3") (pinfunction "I1_3") (pintype "input"))
      (node (ref "E2") (pin "5") (pinfunction "I0_5") (pintype "input"))
      (node (ref "E2") (pin "9") (pinfunction "I1_9") (pintype "input"))
      (node (ref "E33") (pin "5") (pinfunction "I0_5") (pintype "input"))
      (node (ref "E33") (pin "6") (pinfunction "I1_6") (pintype "input"))
      (node (ref "E44") (pin "6") (pinfunction "O_6") (pintype "output"))
    )
    (net (code "30") (name "DOTCF") (class "Default")
      (node (ref "E41") (pin "12") (pinfunction "I0_12") (pintype "input"))
      (node (ref "E41") (pin "8") (pinfunction "O_8") (pintype "output"))
    )
    (net (code "31") (name "DOTPC") (class "Default")
      (node (ref "E25") (pin "3") (pinfunction "I2_3") (pintype "input"))
      (node (ref "E29") (pin "12") (pinfunction "D_12") (pintype "input"))
      (node (ref "E35") (pin "1") (pinfunction "I0_1") (pintype "input"))
      (node (ref "E35") (pin "2") (pinfunction "I1_2") (pintype "input"))
      (node (ref "E41") (pin "6") (pinfunction "O_6") (pintype "output"))
    )
    (net (code "32") (name "EIA_IN") (class "Default")
      (node (ref "E17") (pin "1") (pinfunction "I_1") (pintype "input"))
      (node (ref "J1") (pin "J") (pinfunction "8_J") (pintype "bidirectional"))
    )
    (net (code "33") (name "EIA_OUT") (class "Default")
      (node (ref "E32") (pin "3") (pinfunction "O_3") (pintype "output"))
      (node (ref "J1") (pin "F") (pinfunction "6_F") (pintype "bidirectional"))
    )
    (net (code "34") (name "ENAB") (class "Default")
      (node (ref "E24") (pin "2") (pinfunction "I1_2") (pintype "input"))
      (node (ref "E25") (pin "13") (pinfunction "I3_13") (pintype "input"))
      (node (ref "E28") (pin "4") (pinfunction "D_4") (pintype "input"))
      (node (ref "E29") (pin "9") (pinfunction "Q_9") (pintype "output"))
    )
    (net (code "35") (name "FLGS") (class "Default")
      (node (ref "E37") (pin "11") (pinfunction "I0_11") (pintype "input"))
      (node (ref "E39") (pin "3") (pinfunction "I2_3") (pintype "input"))
      (node (ref "E44") (pin "3") (pinfunction "O_3") (pintype "output"))
    )
    (net (code "36") (name "GND") (class "Default")
      (node (ref "C1") (pin "2") (pinfunction "2_2") (pintype "passive"))
      (node (ref "C10") (pin "2") (pinfunction "2_2") (pintype "passive"))
      (node (ref "C11") (pin "2") (pinfunction "2_2") (pintype "passive"))
      (node (ref "C12") (pin "2") (pinfunction "2_2") (pintype "passive"))
      (node (ref "C13") (pin "2") (pinfunction "2_2") (pintype "passive"))
      (node (ref "C14") (pin "2") (pinfunction "2_2") (pintype "passive"))
      (node (ref "C15") (pin "2") (pinfunction "2_2") (pintype "passive"))
      (node (ref "C16") (pin "2") (pinfunction "2_2") (pintype "passive"))
      (node (ref "C17") (pin "2") (pinfunction "2_2") (pintype "passive"))
      (node (ref "C18") (pin "2") (pinfunction "2_2") (pintype "passive"))
      (node (ref "C19") (pin "2") (pinfunction "2_2") (pintype "passive"))
      (node (ref "C2") (pin "2") (pinfunction "2_2") (pintype "passive"))
      (node (ref "C20") (pin "2") (pinfunction "2_2") (pintype "passive"))
      (node (ref "C21") (pin "2") (pinfunction "2_2") (pintype "passive"))
      (node (ref "C22") (pin "2") (pinfunction "2_2") (pintype "passive"))
      (node (ref "C23") (pin "2") (pinfunction "2_2") (pintype "passive"))
      (node (ref "C24") (pin "2") (pinfunction "2_2") (pintype "passive"))
      (node (ref "C25") (pin "2") (pinfunction "2_2") (pintype "passive"))
      (node (ref "C26") (pin "2") (pinfunction "2_2") (pintype "passive"))
      (node (ref "C27") (pin "2") (pinfunction "2_2") (pintype "passive"))
      (node (ref "C28") (pin "2") (pinfunction "2_2") (pintype "passive"))
      (node (ref "C29") (pin "2") (pinfunction "2_2") (pintype "passive"))
      (node (ref "C3") (pin "2") (pinfunction "2_2") (pintype "passive"))
      (node (ref "C30") (pin "2") (pinfunction "2_2") (pintype "passive"))
      (node (ref "C31") (pin "2") (pinfunction "2_2") (pintype "passive"))
      (node (ref "C32") (pin "2") (pinfunction "2_2") (pintype "passive"))
      (node (ref "C33") (pin "2") (pinfunction "2_2") (pintype "passive"))
      (node (ref "C34") (pin "2") (pinfunction "2_2") (pintype "passive"))
      (node (ref "C35") (pin "2") (pinfunction "2_2") (pintype "passive"))
      (node (ref "C36") (pin "2") (pinfunction "2_2") (pintype "passive"))
      (node (ref "C37") (pin "2") (pinfunction "2_2") (pintype "passive"))
      (node (ref "C38") (pin "2") (pinfunction "2_2") (pintype "passive"))
      (node (ref "C39") (pin "2") (pinfunction "2_2") (pintype "passive"))
      (node (ref "C4") (pin "2") (pinfunction "2_2") (pintype "passive"))
      (node (ref "C40") (pin "2") (pinfunction "2_2") (pintype "passive"))
      (node (ref "C41") (pin "2") (pinfunction "2_2") (pintype "passive"))
      (node (ref "C42") (pin "2") (pinfunction "2_2") (pintype "passive"))
      (node (ref "C43") (pin "2") (pinfunction "2_2") (pintype "passive"))
      (node (ref "C44") (pin "2") (pinfunction "2_2") (pintype "passive"))
      (node (ref "C45") (pin "2") (pinfunction "2_2") (pintype "passive"))
      (node (ref "C46") (pin "2") (pinfunction "2_2") (pintype "passive"))
      (node (ref "C47") (pin "2") (pinfunction "2_2") (pintype "passive"))
      (node (ref "C48") (pin "2") (pinfunction "2_2") (pintype "passive"))
      (node (ref "C49") (pin "2") (pinfunction "2_2") (pintype "passive"))
      (node (ref "C5") (pin "2") (pinfunction "2_2") (pintype "passive"))
      (node (ref "C50") (pin "2") (pinfunction "2_2") (pintype "passive"))
      (node (ref "C51") (pin "-") (pinfunction "-_-") (pintype "passive"))
      (node (ref "C52") (pin "-") (pinfunction "-_-") (pintype "passive"))
      (node (ref "C53") (pin "-") (pinfunction "-_-") (pintype "passive"))
      (node (ref "C54") (pin "-") (pinfunction "-_-") (pintype "passive"))
      (node (ref "C55") (pin "+") (pinfunction "+_+") (pintype "passive"))
      (node (ref "C56") (pin "-") (pinfunction "-_-") (pintype "passive"))
      (node (ref "C57") (pin "2") (pinfunction "2_2") (pintype "passive"))
      (node (ref "C6") (pin "2") (pinfunction "2_2") (pintype "passive"))
      (node (ref "C60") (pin "2") (pinfunction "2_2") (pintype "passive"))
      (node (ref "C62") (pin "2") (pinfunction "2_2") (pintype "passive"))
      (node (ref "C66") (pin "-") (pinfunction "-_-") (pintype "passive"))
      (node (ref "C67") (pin "2") (pinfunction "2_2") (pintype "passive"))
      (node (ref "C7") (pin "2") (pinfunction "2_2") (pintype "passive"))
      (node (ref "C8") (pin "2") (pinfunction "2_2") (pintype "passive"))
      (node (ref "C9") (pin "2") (pinfunction "2_2") (pintype "passive"))
      (node (ref "D1") (pin "C") (pinfunction "C_C") (pintype "passive"))
      (node (ref "D2") (pin "C") (pinfunction "C_C") (pintype "passive"))
      (node (ref "D5") (pin "C") (pinfunction "C_C") (pintype "passive"))
      (node (ref "D8") (pin "A") (pinfunction "A_A") (pintype "passive"))
      (node (ref "DL1") (pin "2") (pinfunction "2_2") (pintype "passive"))
      (node (ref "E13") (pin "2") (pinfunction "R0(1)_2") (pintype "input"))
      (node (ref "E13") (pin "3") (pinfunction "R0(2)_3") (pintype "input"))
      (node (ref "E16") (pin "12") (pinfunction "D_12") (pintype "input"))
      (node (ref "E18") (pin "2") (pinfunction "R0(1)_2") (pintype "input"))
      (node (ref "E18") (pin "3") (pinfunction "R0(2)_3") (pintype "input"))
      (node (ref "E22") (pin "1") (pinfunction "B_1") (pintype "input"))
      (node (ref "E22") (pin "10") (pinfunction "C_10") (pintype "input"))
      (node (ref "E22") (pin "14") (pinfunction "CLR_14") (pintype "input"))
      (node (ref "E22") (pin "15") (pinfunction "A_15") (pintype "input"))
      (node (ref "E22") (pin "9") (pinfunction "D_9") (pintype "input"))
      (node (ref "E3") (pin "12") (pinfunction "D_12") (pintype "input"))
      (node (ref "E32") (pin "4") (pinfunction "I0_4") (pintype "input"))
      (node (ref "E32") (pin "5") (pinfunction "I1_5") (pintype "input"))
      (node (ref "E34") (pin "10") (pinfunction "I1_10") (pintype "input"))
      (node (ref "E34") (pin "11") (pinfunction "I0_11") (pintype "input"))
      (node (ref "E34") (pin "4") (pinfunction "I0_4") (pintype "input"))
      (node (ref "E36") (pin "10") (pinfunction "I1_10") (pintype "input"))
      (node (ref "E36") (pin "11") (pinfunction "I0_11") (pintype "input"))
      (node (ref "E5") (pin "2") (pinfunction "R0(1)_2") (pintype "input"))
      (node (ref "E5") (pin "3") (pinfunction "R0(2)_3") (pintype "input"))
      (node (ref "E7") (pin "12") (pinfunction "D_12") (pintype "input"))
      (node (ref "E7") (pin "2") (pinfunction "D_2") (pintype "input"))
      (node (ref "J1") (pin "A") (pinfunction "1_A") (pintype "bidirectional"))
      (node (ref "J1") (pin "B") (pinfunction "2_B") (pintype "bidirectional"))
      (node (ref "J1") (pin "C") (pinfunction "3_C") (pintype "bidirectional"))
      (node (ref "J1") (pin "UU") (pinfunction "39_UU") (pintype "bidirectional"))
      (node (ref "J1") (pin "VV") (pinfunction "40_VV") (pintype "bidirectional"))
      (node (ref "R2") (pin "1") (pinfunction "1_1") (pintype "passive"))
      (node (ref "R20") (pin "2") (pinfunction "2_2") (pintype "passive"))
      (node (ref "T1") (pin "4") (pinfunction "4_4") (pintype "passive"))
      (node (ref "T1") (pin "8") (pinfunction "8_8") (pintype "passive"))
      (node (ref "U$2") (pin "AC2") (pinfunction "1_AC2") (pintype "bidirectional"))
      (node (ref "U$2") (pin "AF1") (pinfunction "1_AF1") (pintype "bidirectional"))
      (node (ref "U$2") (pin "AF2") (pinfunction "1_AF2") (pintype "bidirectional"))
      (node (ref "U$2") (pin "AN1") (pinfunction "1_AN1") (pintype "bidirectional"))
      (node (ref "U$2") (pin "AN2") (pinfunction "1_AN2") (pintype "bidirectional"))
      (node (ref "U$2") (pin "AT1") (pinfunction "1_AT1") (pintype "bidirectional"))
      (node (ref "U$2") (pin "AT2") (pinfunction "1_AT2") (pintype "bidirectional"))
      (node (ref "U$2") (pin "BC1") (pinfunction "1_BC1") (pintype "bidirectional"))
      (node (ref "U$2") (pin "BC2") (pinfunction "1_BC2") (pintype "bidirectional"))
      (node (ref "U$2") (pin "BF1") (pinfunction "1_BF1") (pintype "bidirectional"))
      (node (ref "U$2") (pin "BF2") (pinfunction "1_BF2") (pintype "bidirectional"))
      (node (ref "U$2") (pin "BN1") (pinfunction "1_BN1") (pintype "bidirectional"))
      (node (ref "U$2") (pin "BN2") (pinfunction "1_BN2") (pintype "bidirectional"))
      (node (ref "U$2") (pin "BT1") (pinfunction "1_BT1") (pintype "bidirectional"))
      (node (ref "U$2") (pin "BT2") (pinfunction "1_BT2") (pintype "bidirectional"))
      (node (ref "U$2") (pin "CC1") (pinfunction "1_CC1") (pintype "bidirectional"))
      (node (ref "U$2") (pin "CC2") (pinfunction "1_CC2") (pintype "bidirectional"))
      (node (ref "U$2") (pin "CF1") (pinfunction "1_CF1") (pintype "bidirectional"))
      (node (ref "U$2") (pin "CF2") (pinfunction "1_CF2") (pintype "bidirectional"))
      (node (ref "U$2") (pin "CN1") (pinfunction "1_CN1") (pintype "bidirectional"))
      (node (ref "U$2") (pin "CN2") (pinfunction "1_CN2") (pintype "bidirectional"))
      (node (ref "U$2") (pin "CT1") (pinfunction "1_CT1") (pintype "bidirectional"))
      (node (ref "U$2") (pin "CT2") (pinfunction "1_CT2") (pintype "bidirectional"))
      (node (ref "U$2") (pin "DC1") (pinfunction "1_DC1") (pintype "bidirectional"))
      (node (ref "U$2") (pin "DC2") (pinfunction "1_DC2") (pintype "bidirectional"))
      (node (ref "U$2") (pin "DF1") (pinfunction "1_DF1") (pintype "bidirectional"))
      (node (ref "U$2") (pin "DF2") (pinfunction "1_DF2") (pintype "bidirectional"))
      (node (ref "U$2") (pin "DN1") (pinfunction "1_DN1") (pintype "bidirectional"))
      (node (ref "U$2") (pin "DN2") (pinfunction "1_DN2") (pintype "bidirectional"))
      (node (ref "U$2") (pin "DT1") (pinfunction "1_DT1") (pintype "bidirectional"))
      (node (ref "U$2") (pin "DT2") (pinfunction "1_DT2") (pintype "bidirectional"))
      (node (ref "Y1") (pin "2") (pinfunction "2_2") (pintype "passive"))
    )
    (net (code "37") (name "INITIALIZE") (class "Default")
      (node (ref "E36") (pin "9") (pinfunction "I0_9") (pintype "input"))
      (node (ref "U$2") (pin "CR1") (pinfunction "1_CR1") (pintype "bidirectional"))
    )
    (net (code "38") (name "INIT_L") (class "Default")
      (node (ref "E20") (pin "4") (pinfunction "PRE_4") (pintype "input"))
      (node (ref "E28") (pin "1") (pinfunction "R_1") (pintype "input"))
      (node (ref "E31") (pin "1") (pinfunction "R_1") (pintype "input"))
      (node (ref "E35") (pin "11") (pinfunction "O_11") (pintype "output"))
      (node (ref "E35") (pin "5") (pinfunction "I1_5") (pintype "input"))
      (node (ref "E38") (pin "13") (pinfunction "CLR_13") (pintype "input"))
      (node (ref "E41") (pin "1") (pinfunction "I0_1") (pintype "input"))
    )
    (net (code "39") (name "INTERNAL_IO_L") (class "Default")
      (node (ref "E37") (pin "1") (pinfunction "O_1") (pintype "open_collector"))
      (node (ref "E37") (pin "4") (pinfunction "O_4") (pintype "open_collector"))
      (node (ref "U$2") (pin "CL1") (pinfunction "1_CL1") (pintype "bidirectional"))
    )
    (net (code "40") (name "INT_ENAB") (class "Default")
      (node (ref "E37") (pin "12") (pinfunction "I1_12") (pintype "input"))
      (node (ref "E38") (pin "8") (pinfunction "~{Q}_8") (pintype "output"))
      (node (ref "U$2") (pin "CB1") (pinfunction "1_CB1") (pintype "bidirectional"))
    )
    (net (code "41") (name "INT_RQST_L") (class "Default")
      (node (ref "E37") (pin "13") (pinfunction "O_13") (pintype "open_collector"))
      (node (ref "U$2") (pin "CP1") (pinfunction "1_CP1") (pintype "bidirectional"))
    )
    (net (code "42") (name "IO_PAUSE_L") (class "Default")
      (node (ref "E34") (pin "12") (pinfunction "I1_12") (pintype "input"))
      (node (ref "U$2") (pin "CD1") (pinfunction "1_CD1") (pintype "bidirectional"))
    )
    (net (code "43") (name "KSKP") (class "Default")
      (node (ref "E45") (pin "5") (pinfunction "I0_5") (pintype "input"))
      (node (ref "E47") (pin "13") (pinfunction "O_13") (pintype "output"))
    )
    (net (code "44") (name "LAST_UNIT") (class "Default")
      (node (ref "E39") (pin "13") (pinfunction "I3_13") (pintype "input"))
      (node (ref "E8") (pin "5") (pinfunction "Q_5") (pintype "output"))
    )
    (net (code "45") (name "LINE") (class "Default")
      (node (ref "E29") (pin "5") (pinfunction "Q_5") (pintype "output"))
      (node (ref "E32") (pin "2") (pinfunction "I_2") (pintype "input"))
      (node (ref "U$2") (pin "DA1") (pinfunction "1_DA1") (pintype "bidirectional"))
    )
    (net (code "46") (name "MD03") (class "Default")
      (node (ref "B") (pin "4") (pinfunction "4_4") (pintype "passive"))
      (node (ref "E1") (pin "10") (pinfunction "I1_10") (pintype "input"))
      (node (ref "U$2") (pin "AP1") (pinfunction "1_AP1") (pintype "bidirectional"))
    )
    (net (code "47") (name "MD04") (class "Default")
      (node (ref "A") (pin "4") (pinfunction "4_4") (pintype "passive"))
      (node (ref "E1") (pin "7") (pinfunction "I1_7") (pintype "input"))
      (node (ref "U$2") (pin "BK1") (pinfunction "1_BK1") (pintype "bidirectional"))
    )
    (net (code "48") (name "MD05") (class "Default")
      (node (ref "E23") (pin "9") (pinfunction "I0_9") (pintype "input"))
      (node (ref "F") (pin "3") (pinfunction "3_3") (pintype "passive"))
      (node (ref "U$2") (pin "BL1") (pinfunction "1_BL1") (pintype "bidirectional"))
    )
    (net (code "49") (name "MD06") (class "Default")
      (node (ref "E") (pin "3") (pinfunction "3_3") (pintype "passive"))
      (node (ref "E23") (pin "12") (pinfunction "I1_12") (pintype "input"))
      (node (ref "JE13") (pin "1") (pinfunction "1_1") (pintype "passive"))
      (node (ref "U$2") (pin "BM1") (pinfunction "1_BM1") (pintype "bidirectional"))
    )
    (net (code "50") (name "MD07") (class "Default")
      (node (ref "D") (pin "4") (pinfunction "4_4") (pintype "passive"))
      (node (ref "E23") (pin "7") (pinfunction "I1_7") (pintype "input"))
      (node (ref "JD24") (pin "1") (pinfunction "1_1") (pintype "passive"))
      (node (ref "U$2") (pin "BP1") (pinfunction "1_BP1") (pintype "bidirectional"))
    )
    (net (code "51") (name "MD08") (class "Default")
      (node (ref "C") (pin "4") (pinfunction "4_4") (pintype "passive"))
      (node (ref "E1") (pin "4") (pinfunction "I0_4") (pintype "input"))
      (node (ref "JC24") (pin "1") (pinfunction "1_1") (pintype "passive"))
      (node (ref "U$2") (pin "DK1") (pinfunction "1_DK1") (pintype "bidirectional"))
    )
    (net (code "52") (name "MD09") (class "Default")
      (node (ref "E46") (pin "7") (pinfunction "I1_7") (pintype "input"))
      (node (ref "U$2") (pin "DL1") (pinfunction "1_DL1") (pintype "bidirectional"))
    )
    (net (code "53") (name "MD10") (class "Default")
      (node (ref "E46") (pin "4") (pinfunction "I0_4") (pintype "input"))
      (node (ref "U$2") (pin "DM1") (pinfunction "1_DM1") (pintype "bidirectional"))
    )
    (net (code "54") (name "MD11") (class "Default")
      (node (ref "E46") (pin "9") (pinfunction "I0_9") (pintype "input"))
      (node (ref "U$2") (pin "DP1") (pinfunction "1_DP1") (pintype "bidirectional"))
    )
    (net (code "55") (name "N$18") (class "Default")
      (node (ref "E19") (pin "6") (pinfunction "O_6") (pintype "output"))
      (node (ref "E25") (pin "10") (pinfunction "I1_10") (pintype "input"))
    )
    (net (code "56") (name "N$24") (class "Default")
      (node (ref "E19") (pin "8") (pinfunction "O_8") (pintype "output"))
      (node (ref "E38") (pin "2") (pinfunction "D_2") (pintype "input"))
    )
    (net (code "57") (name "N$27") (class "Default")
      (node (ref "E12") (pin "10") (pinfunction "I1_10") (pintype "input"))
      (node (ref "E12") (pin "11") (pinfunction "O_11") (pintype "output"))
      (node (ref "E21") (pin "11") (pinfunction "I_11") (pintype "input"))
      (node (ref "E36") (pin "4") (pinfunction "I0_4") (pintype "input"))
      (node (ref "E36") (pin "5") (pinfunction "I1_5") (pintype "input"))
      (node (ref "R15") (pin "1") (pinfunction "1_1") (pintype "passive"))
    )
    (net (code "58") (name "N$30") (class "Default")
      (node (ref "E1") (pin "11") (pinfunction "I0_11") (pintype "input"))
      (node (ref "E1") (pin "12") (pinfunction "I1_12") (pintype "input"))
      (node (ref "E2") (pin "12") (pinfunction "I1_12") (pintype "input"))
      (node (ref "E6") (pin "5") (pinfunction "Q0_5") (pintype "output"))
      (node (ref "R24") (pin "1") (pinfunction "1_1") (pintype "passive"))
    )
    (net (code "59") (name "N$43") (class "Default")
      (node (ref "E11") (pin "9") (pinfunction "I1_9") (pintype "input"))
      (node (ref "E4") (pin "11") (pinfunction "CLK_11") (pintype "input"))
      (node (ref "E4") (pin "2") (pinfunction "D_2") (pintype "input"))
      (node (ref "E4") (pin "6") (pinfunction "~{Q}_6") (pintype "output"))
    )
    (net (code "60") (name "N$57") (class "Default")
      (node (ref "E21") (pin "3") (pinfunction "I_3") (pintype "input"))
      (node (ref "E25") (pin "6") (pinfunction "O_6") (pintype "output"))
      (node (ref "E28") (pin "6") (pinfunction "C_6") (pintype "input"))
      (node (ref "E31") (pin "6") (pinfunction "C_6") (pintype "input"))
    )
    (net (code "61") (name "N$71") (class "Default")
      (node (ref "E16") (pin "10") (pinfunction "PRE_10") (pintype "input"))
      (node (ref "E19") (pin "12") (pinfunction "O_12") (pintype "output"))
      (node (ref "E7") (pin "4") (pinfunction "PRE_4") (pintype "input"))
    )
    (net (code "62") (name "N$75") (class "Default")
      (node (ref "E4") (pin "12") (pinfunction "D_12") (pintype "input"))
      (node (ref "E4") (pin "8") (pinfunction "~{Q}_8") (pintype "output"))
      (node (ref "E7") (pin "10") (pinfunction "PRE_10") (pintype "input"))
      (node (ref "E8") (pin "11") (pinfunction "CLK_11") (pintype "input"))
    )
    (net (code "63") (name "N$80") (class "Default")
      (node (ref "E11") (pin "11") (pinfunction "I0_11") (pintype "input"))
      (node (ref "E11") (pin "12") (pinfunction "I1_12") (pintype "input"))
      (node (ref "E12") (pin "3") (pinfunction "O_3") (pintype "output"))
      (node (ref "E16") (pin "11") (pinfunction "CLK_11") (pintype "input"))
      (node (ref "E39") (pin "1") (pinfunction "I4_1") (pintype "input"))
    )
    (net (code "64") (name "N$85") (class "Default")
      (node (ref "E36") (pin "3") (pinfunction "O_3") (pintype "output"))
      (node (ref "E4") (pin "1") (pinfunction "CLR_1") (pintype "input"))
      (node (ref "E4") (pin "13") (pinfunction "CLR_13") (pintype "input"))
      (node (ref "E8") (pin "13") (pinfunction "CLR_13") (pintype "input"))
    )
    (net (code "65") (name "N$88") (class "Default")
      (node (ref "E12") (pin "2") (pinfunction "I1_2") (pintype "input"))
      (node (ref "E12") (pin "5") (pinfunction "I1_5") (pintype "input"))
      (node (ref "E8") (pin "9") (pinfunction "Q_9") (pintype "output"))
    )
    (net (code "66") (name "Net-(C58-Pad2)") (class "Default")
      (node (ref "C58") (pin "2") (pinfunction "2_2") (pintype "passive"))
      (node (ref "C67") (pin "1") (pinfunction "1_1") (pintype "passive"))
      (node (ref "Y1") (pin "1") (pinfunction "1_1") (pintype "passive"))
    )
    (net (code "67") (name "Net-(C61-Pad2)") (class "Default")
      (node (ref "C61") (pin "2") (pinfunction "2_2") (pintype "passive"))
      (node (ref "R4") (pin "2") (pinfunction "2_2") (pintype "passive"))
      (node (ref "T1") (pin "1") (pinfunction "1_1") (pintype "passive"))
      (node (ref "T1") (pin "5") (pinfunction "5_5") (pintype "passive"))
    )
    (net (code "68") (name "Net-(C66-Pad+)") (class "Default")
      (node (ref "C66") (pin "+") (pinfunction "+_+") (pintype "passive"))
      (node (ref "D7") (pin "A") (pinfunction "A_A") (pintype "passive"))
      (node (ref "D8") (pin "C") (pinfunction "C_C") (pintype "passive"))
      (node (ref "R18") (pin "1") (pinfunction "1_1") (pintype "passive"))
      (node (ref "R22") (pin "2") (pinfunction "2_2") (pintype "passive"))
    )
    (net (code "69") (name "Net-(D1-PadA)") (class "Default")
      (node (ref "D1") (pin "A") (pinfunction "A_A") (pintype "passive"))
      (node (ref "R5") (pin "1") (pinfunction "1_1") (pintype "passive"))
      (node (ref "R7") (pin "1") (pinfunction "1_1") (pintype "passive"))
      (node (ref "T1") (pin "9") (pinfunction "9_9") (pintype "passive"))
    )
    (net (code "70") (name "Net-(D2-PadA)") (class "Default")
      (node (ref "D2") (pin "A") (pinfunction "A_A") (pintype "passive"))
      (node (ref "D3") (pin "C") (pinfunction "C_C") (pintype "passive"))
    )
    (net (code "71") (name "Net-(D3-PadA)") (class "Default")
      (node (ref "D3") (pin "A") (pinfunction "A_A") (pintype "passive"))
      (node (ref "D4") (pin "C") (pinfunction "C_C") (pintype "passive"))
    )
    (net (code "72") (name "Net-(D10-PadC)") (class "Default")
      (node (ref "D10") (pin "C") (pinfunction "C_C") (pintype "passive"))
      (node (ref "D11") (pin "A") (pinfunction "A_A") (pintype "passive"))
    )
    (net (code "73") (name "Net-(D11-PadC)") (class "Default")
      (node (ref "D11") (pin "C") (pinfunction "C_C") (pintype "passive"))
      (node (ref "D12") (pin "A") (pinfunction "A_A") (pintype "passive"))
    )
    (net (code "74") (name "Net-(D13-PadA)") (class "Default")
      (node (ref "D13") (pin "A") (pinfunction "A_A") (pintype "passive"))
      (node (ref "D14") (pin "C") (pinfunction "C_C") (pintype "passive"))
    )
    (net (code "75") (name "Net-(D14-PadA)") (class "Default")
      (node (ref "D14") (pin "A") (pinfunction "A_A") (pintype "passive"))
      (node (ref "D15") (pin "C") (pinfunction "C_C") (pintype "passive"))
    )
    (net (code "76") (name "Net-(E1A-O)") (class "Default")
      (node (ref "C") (pin "1") (pinfunction "1_1") (pintype "passive"))
      (node (ref "E1") (pin "3") (pinfunction "O_3") (pintype "output"))
      (node (ref "JC13") (pin "2") (pinfunction "2_2") (pintype "passive"))
    )
    (net (code "77") (name "Net-(E1B-O)") (class "Default")
      (node (ref "A") (pin "1") (pinfunction "1_1") (pintype "passive"))
      (node (ref "E1") (pin "2") (pinfunction "O_2") (pintype "output"))
      (node (ref "JA12") (pin "1") (pinfunction "1_1") (pintype "passive"))
      (node (ref "JA13") (pin "2") (pinfunction "2_2") (pintype "passive"))
    )
    (net (code "78") (name "Net-(E1C-O)") (class "Default")
      (node (ref "B") (pin "1") (pinfunction "1_1") (pintype "passive"))
      (node (ref "E1") (pin "14") (pinfunction "O_14") (pintype "output"))
      (node (ref "JB12") (pin "1") (pinfunction "1_1") (pintype "passive"))
      (node (ref "JB13") (pin "2") (pinfunction "2_2") (pintype "passive"))
    )
    (net (code "79") (name "Net-(E1D-O)") (class "Default")
      (node (ref "E1") (pin "13") (pinfunction "O_13") (pintype "output"))
      (node (ref "E48") (pin "11") (pinfunction "CLK_11") (pintype "input"))
    )
    (net (code "80") (name "Net-(E2B-I1)") (class "Default")
      (node (ref "E2") (pin "6") (pinfunction "I1_6") (pintype "input"))
      (node (ref "E6") (pin "9") (pinfunction "Q2_9") (pintype "output"))
    )
    (net (code "81") (name "Net-(E2C-I0)") (class "Default")
      (node (ref "E2") (pin "8") (pinfunction "I0_8") (pintype "input"))
      (node (ref "E6") (pin "7") (pinfunction "Q1_7") (pintype "output"))
    )
    (net (code "82") (name "Net-(E5A-CKB)") (class "Default")
      (node (ref "E5") (pin "1") (pinfunction "CKB_1") (pintype "input"))
      (node (ref "E5") (pin "12") (pinfunction "QA_12") (pintype "output"))
    )
    (net (code "83") (name "Net-(E8B-D)") (class "Default")
      (node (ref "E8") (pin "12") (pinfunction "D_12") (pintype "input"))
      (node (ref "E8") (pin "8") (pinfunction "~{Q}_8") (pintype "output"))
    )
    (net (code "84") (name "Net-(E9A-I0)") (class "Default")
      (node (ref "E9") (pin "4") (pinfunction "I0_4") (pintype "input"))
      (node (ref "F") (pin "1") (pinfunction "1_1") (pintype "passive"))
      (node (ref "JF12") (pin "2") (pinfunction "2_2") (pintype "passive"))
    )
    (net (code "85") (name "Net-(E9A-I2)") (class "Default")
      (node (ref "E") (pin "4") (pinfunction "4_4") (pintype "passive"))
      (node (ref "E9") (pin "6") (pinfunction "I2_6") (pintype "input"))
      (node (ref "JE24") (pin "1") (pinfunction "1_1") (pintype "passive"))
    )
    (net (code "86") (name "Net-(E9A-I3)") (class "Default")
      (node (ref "A") (pin "3") (pinfunction "3_3") (pintype "passive"))
      (node (ref "E9") (pin "9") (pinfunction "I3_9") (pintype "input"))
      (node (ref "JA13") (pin "1") (pinfunction "1_1") (pintype "passive"))
    )
    (net (code "87") (name "Net-(E9A-I4)") (class "Default")
      (node (ref "C") (pin "2") (pinfunction "2_2") (pintype "passive"))
      (node (ref "E9") (pin "10") (pinfunction "I4_10") (pintype "input"))
      (node (ref "JC24") (pin "2") (pinfunction "2_2") (pintype "passive"))
    )
    (net (code "88") (name "Net-(E9A-I5)") (class "Default")
      (node (ref "B") (pin "2") (pinfunction "2_2") (pintype "passive"))
      (node (ref "E9") (pin "11") (pinfunction "I5_11") (pintype "input"))
      (node (ref "JB12") (pin "2") (pinfunction "2_2") (pintype "passive"))
    )
    (net (code "89") (name "Net-(E9A-I6)") (class "Default")
      (node (ref "D") (pin "2") (pinfunction "2_2") (pintype "passive"))
      (node (ref "E9") (pin "12") (pinfunction "I6_12") (pintype "input"))
      (node (ref "JD24") (pin "2") (pinfunction "2_2") (pintype "passive"))
    )
    (net (code "90") (name "Net-(E10A-C)") (class "Default")
      (node (ref "E10") (pin "6") (pinfunction "C_6") (pintype "input"))
      (node (ref "E11") (pin "4") (pinfunction "O_4") (pintype "output"))
      (node (ref "E6") (pin "6") (pinfunction "C_6") (pintype "input"))
    )
    (net (code "91") (name "Net-(E10A-D)") (class "Default")
      (node (ref "E10") (pin "4") (pinfunction "D_4") (pintype "input"))
      (node (ref "E2") (pin "2") (pinfunction "I0_2") (pintype "input"))
      (node (ref "E6") (pin "11") (pinfunction "Q3_11") (pintype "output"))
    )
    (net (code "92") (name "Net-(E10A-Q0)") (class "Default")
      (node (ref "E10") (pin "5") (pinfunction "Q0_5") (pintype "output"))
      (node (ref "E15") (pin "12") (pinfunction "I1_12") (pintype "input"))
    )
    (net (code "93") (name "Net-(E10A-Q1)") (class "Default")
      (node (ref "E10") (pin "7") (pinfunction "Q1_7") (pintype "output"))
      (node (ref "E15") (pin "8") (pinfunction "I0_8") (pintype "input"))
    )
    (net (code "94") (name "Net-(E10A-Q2)") (class "Default")
      (node (ref "E10") (pin "9") (pinfunction "Q2_9") (pintype "output"))
      (node (ref "E15") (pin "6") (pinfunction "I1_6") (pintype "input"))
    )
    (net (code "95") (name "Net-(E10A-Q3)") (class "Default")
      (node (ref "E10") (pin "11") (pinfunction "Q3_11") (pintype "output"))
      (node (ref "E15") (pin "2") (pinfunction "I0_2") (pintype "input"))
    )
    (net (code "96") (name "Net-(E11A-O)") (class "Default")
      (node (ref "E11") (pin "1") (pinfunction "O_1") (pintype "output"))
      (node (ref "E39") (pin "9") (pinfunction "I2_9") (pintype "input"))
    )
    (net (code "97") (name "Net-(E11B-I1)") (class "Default")
      (node (ref "E11") (pin "10") (pinfunction "O_10") (pintype "output"))
      (node (ref "E11") (pin "6") (pinfunction "I1_6") (pintype "input"))
    )
    (net (code "98") (name "Net-(E11D-O)") (class "Default")
      (node (ref "E11") (pin "13") (pinfunction "O_13") (pintype "output"))
      (node (ref "E3") (pin "11") (pinfunction "CLK_11") (pintype "input"))
    )
    (net (code "99") (name "Net-(E12B-O)") (class "Default")
      (node (ref "E12") (pin "6") (pinfunction "O_6") (pintype "output"))
      (node (ref "E8") (pin "1") (pinfunction "CLR_1") (pintype "input"))
    )
    (net (code "100") (name "Net-(E12C-O)") (class "Default")
      (node (ref "E12") (pin "8") (pinfunction "O_8") (pintype "output"))
      (node (ref "E3") (pin "2") (pinfunction "D_2") (pintype "input"))
    )
    (net (code "101") (name "Net-(E14A-I0)") (class "Default")
      (node (ref "E") (pin "1") (pinfunction "1_1") (pintype "passive"))
      (node (ref "E14") (pin "4") (pinfunction "I0_4") (pintype "input"))
      (node (ref "JE13") (pin "2") (pinfunction "2_2") (pintype "passive"))
    )
    (net (code "102") (name "Net-(E14A-I1)") (class "Default")
      (node (ref "E14") (pin "5") (pinfunction "I1_5") (pintype "input"))
      (node (ref "F") (pin "4") (pinfunction "4_4") (pintype "passive"))
      (node (ref "JF24") (pin "1") (pinfunction "1_1") (pintype "passive"))
    )
    (net (code "103") (name "Net-(E14A-I2)") (class "Default")
      (node (ref "D") (pin "3") (pinfunction "3_3") (pintype "passive"))
      (node (ref "E14") (pin "6") (pinfunction "I2_6") (pintype "input"))
      (node (ref "JD13") (pin "1") (pinfunction "1_1") (pintype "passive"))
    )
    (net (code "104") (name "Net-(E14A-I3)") (class "Default")
      (node (ref "B") (pin "3") (pinfunction "3_3") (pintype "passive"))
      (node (ref "E14") (pin "9") (pinfunction "I3_9") (pintype "input"))
      (node (ref "JB13") (pin "1") (pinfunction "1_1") (pintype "passive"))
    )
    (net (code "105") (name "Net-(E14A-I4)") (class "Default")
      (node (ref "C") (pin "3") (pinfunction "3_3") (pintype "passive"))
      (node (ref "E14") (pin "10") (pinfunction "I4_10") (pintype "input"))
      (node (ref "JC13") (pin "1") (pinfunction "1_1") (pintype "passive"))
    )
    (net (code "106") (name "Net-(E14A-I5)") (class "Default")
      (node (ref "E14") (pin "11") (pinfunction "I5_11") (pintype "input"))
      (node (ref "E34") (pin "3") (pinfunction "O_3") (pintype "output"))
      (node (ref "E34") (pin "6") (pinfunction "I0_6") (pintype "input"))
      (node (ref "E9") (pin "5") (pinfunction "I1_5") (pintype "input"))
    )
    (net (code "107") (name "Net-(E14A-I6)") (class "Default")
      (node (ref "A") (pin "2") (pinfunction "2_2") (pintype "passive"))
      (node (ref "E14") (pin "12") (pinfunction "I6_12") (pintype "input"))
      (node (ref "JA12") (pin "2") (pinfunction "2_2") (pintype "passive"))
    )
    (net (code "108") (name "Net-(E14A-O)") (class "Default")
      (node (ref "E14") (pin "3") (pinfunction "O_3") (pintype "output"))
      (node (ref "E23") (pin "5") (pinfunction "I1_5") (pintype "input"))
      (node (ref "E33") (pin "8") (pinfunction "I0_8") (pintype "input"))
      (node (ref "E33") (pin "9") (pinfunction "I1_9") (pintype "input"))
      (node (ref "E37") (pin "2") (pinfunction "I0_2") (pintype "input"))
      (node (ref "E37") (pin "3") (pinfunction "I1_3") (pintype "input"))
    )
    (net (code "109") (name "Net-(E16A-D)") (class "Default")
      (node (ref "E16") (pin "2") (pinfunction "D_2") (pintype "input"))
      (node (ref "E35") (pin "8") (pinfunction "O_8") (pintype "output"))
    )
    (net (code "110") (name "Net-(E17A-O)") (class "Default")
      (node (ref "E17") (pin "3") (pinfunction "O_3") (pintype "output"))
      (node (ref "E21") (pin "13") (pinfunction "I_13") (pintype "input"))
    )
    (net (code "111") (name "Net-(E17A-RC)") (class "Default")
      (node (ref "E17") (pin "2") (pinfunction "RC_2") (pintype "input"))
      (node (ref "R23") (pin "1") (pinfunction "1_1") (pintype "passive"))
    )
    (net (code "112") (name "Net-(E18A-CKA)") (class "Default")
      (node (ref "E18") (pin "14") (pinfunction "CKA_14") (pintype "input"))
      (node (ref "G12") (pin "2") (pinfunction "2_2") (pintype "passive"))
      (node (ref "G34") (pin "2") (pinfunction "2_2") (pintype "passive"))
      (node (ref "G56") (pin "2") (pinfunction "2_2") (pintype "passive"))
      (node (ref "G78") (pin "2") (pinfunction "2_2") (pintype "passive"))
      (node (ref "G910") (pin "2") (pinfunction "2_2") (pintype "passive"))
      (node (ref "U$2") (pin "AA1") (pinfunction "1_AA1") (pintype "bidirectional"))
    )
    (net (code "113") (name "Net-(E18A-QD)") (class "Default")
      (node (ref "E18") (pin "11") (pinfunction "QD_11") (pintype "output"))
      (node (ref "H12") (pin "1") (pinfunction "1_1") (pintype "passive"))
      (node (ref "H123") (pin "1") (pinfunction "1_1") (pintype "passive"))
    )
    (net (code "114") (name "Net-(E19A-I1)") (class "Default")
      (node (ref "E19") (pin "2") (pinfunction "I1_2") (pintype "input"))
      (node (ref "E21") (pin "10") (pinfunction "O_10") (pintype "output"))
    )
    (net (code "115") (name "Net-(E19B-I0)") (class "Default")
      (node (ref "E19") (pin "11") (pinfunction "I2_11") (pintype "input"))
      (node (ref "E19") (pin "3") (pinfunction "I0_3") (pintype "input"))
      (node (ref "E24") (pin "8") (pinfunction "O_8") (pintype "output"))
    )
    (net (code "116") (name "Net-(E19B-I2)") (class "Default")
      (node (ref "E19") (pin "10") (pinfunction "I1_10") (pintype "input"))
      (node (ref "E19") (pin "5") (pinfunction "I2_5") (pintype "input"))
      (node (ref "E19") (pin "9") (pinfunction "I0_9") (pintype "input"))
      (node (ref "E24") (pin "6") (pinfunction "O_6") (pintype "output"))
    )
    (net (code "117") (name "Net-(E20A-D)") (class "Default")
      (node (ref "E20") (pin "2") (pinfunction "D_2") (pintype "input"))
      (node (ref "E25") (pin "8") (pinfunction "O_8") (pintype "output"))
    )
    (net (code "118") (name "Net-(E21A-I)") (class "Default")
      (node (ref "E21") (pin "1") (pinfunction "I_1") (pintype "input"))
      (node (ref "E39") (pin "8") (pinfunction "O_8") (pintype "output"))
    )
    (net (code "119") (name "Net-(E21A-O)") (class "Default")
      (node (ref "E21") (pin "2") (pinfunction "O_2") (pintype "output"))
      (node (ref "E7") (pin "3") (pinfunction "CLK_3") (pintype "input"))
    )
    (net (code "120") (name "Net-(E21B-O)") (class "Default")
      (node (ref "E21") (pin "4") (pinfunction "O_4") (pintype "output"))
      (node (ref "E29") (pin "11") (pinfunction "CLK_11") (pintype "input"))
    )
    (net (code "121") (name "Net-(E21C-O)") (class "Default")
      (node (ref "E21") (pin "6") (pinfunction "O_6") (pintype "output"))
      (node (ref "E26") (pin "6") (pinfunction "C_6") (pintype "input"))
    )
    (net (code "122") (name "Net-(E21D-O)") (class "Default")
      (node (ref "E21") (pin "8") (pinfunction "O_8") (pintype "output"))
      (node (ref "E6") (pin "4") (pinfunction "D_4") (pintype "input"))
    )
    (net (code "123") (name "Net-(E22A-QD)") (class "Default")
      (node (ref "E22") (pin "7") (pinfunction "QD_7") (pintype "output"))
      (node (ref "E5") (pin "14") (pinfunction "CKA_14") (pintype "input"))
    )
    (net (code "124") (name "Net-(E22A-UP)") (class "Default")
      (node (ref "E22") (pin "5") (pinfunction "UP_5") (pintype "input"))
      (node (ref "R6") (pin "2") (pinfunction "2_2") (pintype "passive"))
    )
    (net (code "125") (name "Net-(E23A-I0)") (class "Default")
      (node (ref "E23") (pin "4") (pinfunction "I0_4") (pintype "input"))
      (node (ref "E37") (pin "5") (pinfunction "I0_5") (pintype "input"))
      (node (ref "E37") (pin "6") (pinfunction "I1_6") (pintype "input"))
      (node (ref "E42") (pin "13") (pinfunction "I_13") (pintype "input"))
      (node (ref "E9") (pin "3") (pinfunction "O_3") (pintype "output"))
    )
    (net (code "126") (name "Net-(E23B-O)") (class "Default")
      (node (ref "D") (pin "1") (pinfunction "1_1") (pintype "passive"))
      (node (ref "E23") (pin "2") (pinfunction "O_2") (pintype "output"))
      (node (ref "JD13") (pin "2") (pinfunction "2_2") (pintype "passive"))
    )
    (net (code "127") (name "Net-(E23C-O)") (class "Default")
      (node (ref "E23") (pin "14") (pinfunction "O_14") (pintype "output"))
      (node (ref "F") (pin "2") (pinfunction "2_2") (pintype "passive"))
      (node (ref "JF12") (pin "1") (pinfunction "1_1") (pintype "passive"))
      (node (ref "JF24") (pin "2") (pinfunction "2_2") (pintype "passive"))
    )
    (net (code "128") (name "Net-(E23D-O)") (class "Default")
      (node (ref "E") (pin "2") (pinfunction "2_2") (pintype "passive"))
      (node (ref "E23") (pin "13") (pinfunction "O_13") (pintype "output"))
      (node (ref "JE24") (pin "2") (pinfunction "2_2") (pintype "passive"))
    )
    (net (code "129") (name "Net-(E24A-I0)") (class "Default")
      (node (ref "E24") (pin "1") (pinfunction "I0_1") (pintype "input"))
      (node (ref "E28") (pin "9") (pinfunction "Q2_9") (pintype "output"))
    )
    (net (code "130") (name "Net-(E24A-I2)") (class "Default")
      (node (ref "E24") (pin "4") (pinfunction "I2_4") (pintype "input"))
      (node (ref "E28") (pin "5") (pinfunction "Q0_5") (pintype "output"))
    )
    (net (code "131") (name "Net-(E24A-I3)") (class "Default")
      (node (ref "E24") (pin "5") (pinfunction "I3_5") (pintype "input"))
      (node (ref "E28") (pin "7") (pinfunction "Q1_7") (pintype "output"))
    )
    (net (code "132") (name "Net-(E24B-I0)") (class "Default")
      (node (ref "E24") (pin "9") (pinfunction "I0_9") (pintype "input"))
      (node (ref "E31") (pin "5") (pinfunction "Q0_5") (pintype "output"))
    )
    (net (code "133") (name "Net-(E24B-I1)") (class "Default")
      (node (ref "E24") (pin "10") (pinfunction "I1_10") (pintype "input"))
      (node (ref "E31") (pin "7") (pinfunction "Q1_7") (pintype "output"))
    )
    (net (code "134") (name "Net-(E24B-I2)") (class "Default")
      (node (ref "E24") (pin "12") (pinfunction "I2_12") (pintype "input"))
      (node (ref "E31") (pin "9") (pinfunction "Q2_9") (pintype "output"))
    )
    (net (code "135") (name "Net-(E24B-I3)") (class "Default")
      (node (ref "E24") (pin "13") (pinfunction "I3_13") (pintype "input"))
      (node (ref "E28") (pin "11") (pinfunction "Q3_11") (pintype "output"))
      (node (ref "E31") (pin "4") (pinfunction "D_4") (pintype "input"))
    )
    (net (code "136") (name "Net-(E25B-I4)") (class "Default")
      (node (ref "DL1") (pin "3") (pinfunction "3_3") (pintype "passive"))
      (node (ref "E25") (pin "5") (pinfunction "I4_5") (pintype "input"))
      (node (ref "R20") (pin "1") (pinfunction "1_1") (pintype "passive"))
    )
    (net (code "137") (name "Net-(E26A-Q0)") (class "Default")
      (node (ref "E26") (pin "5") (pinfunction "Q0_5") (pintype "output"))
      (node (ref "J23") (pin "3") (pinfunction "3_3") (pintype "passive"))
    )
    (net (code "138") (name "Net-(E26A-Q2)") (class "Default")
      (node (ref "E26") (pin "9") (pinfunction "Q2_9") (pintype "output"))
      (node (ref "J23") (pin "1") (pinfunction "1_1") (pintype "passive"))
      (node (ref "JJ23") (pin "1") (pinfunction "1_1") (pintype "passive"))
    )
    (net (code "139") (name "Net-(E27A-O)") (class "Default")
      (node (ref "E27") (pin "3") (pinfunction "O_3") (pintype "output"))
      (node (ref "E28") (pin "2") (pinfunction "I1_2") (pintype "input"))
    )
    (net (code "140") (name "Net-(E27B-O)") (class "Default")
      (node (ref "E27") (pin "2") (pinfunction "O_2") (pintype "output"))
      (node (ref "E28") (pin "3") (pinfunction "I0_3") (pintype "input"))
    )
    (net (code "141") (name "Net-(E27C-O)") (class "Default")
      (node (ref "E27") (pin "14") (pinfunction "O_14") (pintype "output"))
      (node (ref "E28") (pin "14") (pinfunction "I3_14") (pintype "input"))
    )
    (net (code "142") (name "Net-(E27D-O)") (class "Default")
      (node (ref "E27") (pin "13") (pinfunction "O_13") (pintype "output"))
      (node (ref "E28") (pin "15") (pinfunction "I2_15") (pintype "input"))
    )
    (net (code "143") (name "Net-(E30A-O)") (class "Default")
      (node (ref "E30") (pin "3") (pinfunction "O_3") (pintype "output"))
      (node (ref "E31") (pin "2") (pinfunction "I1_2") (pintype "input"))
    )
    (net (code "144") (name "Net-(E30B-O)") (class "Default")
      (node (ref "E30") (pin "2") (pinfunction "O_2") (pintype "output"))
      (node (ref "E31") (pin "3") (pinfunction "I0_3") (pintype "input"))
    )
    (net (code "145") (name "Net-(E30C-O)") (class "Default")
      (node (ref "E30") (pin "14") (pinfunction "O_14") (pintype "output"))
      (node (ref "E31") (pin "14") (pinfunction "I3_14") (pintype "input"))
    )
    (net (code "146") (name "Net-(E30D-O)") (class "Default")
      (node (ref "E30") (pin "13") (pinfunction "O_13") (pintype "output"))
      (node (ref "E31") (pin "15") (pinfunction "I2_15") (pintype "input"))
    )
    (net (code "147") (name "Net-(E34B-O)") (class "Default")
      (node (ref "E34") (pin "2") (pinfunction "O_2") (pintype "output"))
      (node (ref "E38") (pin "12") (pinfunction "D_12") (pintype "input"))
    )
    (net (code "148") (name "Net-(E35B-O)") (class "Default")
      (node (ref "E35") (pin "6") (pinfunction "O_6") (pintype "output"))
      (node (ref "E47") (pin "2") (pinfunction "I0_2") (pintype "input"))
    )
    (net (code "149") (name "Net-(E35D-I0)") (class "Default")
      (node (ref "E35") (pin "12") (pinfunction "I0_12") (pintype "input"))
      (node (ref "E35") (pin "13") (pinfunction "I1_13") (pintype "input"))
      (node (ref "E36") (pin "14") (pinfunction "O_14") (pintype "output"))
      (node (ref "E46") (pin "11") (pinfunction "I0_11") (pintype "input"))
      (node (ref "E46") (pin "12") (pinfunction "I1_12") (pintype "input"))
    )
    (net (code "150") (name "Net-(E36B-I0)") (class "Default")
      (node (ref "C65") (pin "1") (pinfunction "1_1") (pintype "passive"))
      (node (ref "E36") (pin "6") (pinfunction "I0_6") (pintype "input"))
      (node (ref "E36") (pin "7") (pinfunction "I1_7") (pintype "input"))
      (node (ref "R18") (pin "2") (pinfunction "2_2") (pintype "passive"))
      (node (ref "R19") (pin "1") (pinfunction "1_1") (pintype "passive"))
    )
    (net (code "151") (name "Net-(E36D-O)") (class "Default")
      (node (ref "E36") (pin "13") (pinfunction "O_13") (pintype "output"))
      (node (ref "E7") (pin "1") (pinfunction "CLR_1") (pintype "input"))
    )
    (net (code "152") (name "Net-(E37C-I0)") (class "Default")
      (node (ref "E37") (pin "8") (pinfunction "I0_8") (pintype "input"))
      (node (ref "E37") (pin "9") (pinfunction "I1_9") (pintype "input"))
      (node (ref "E42") (pin "8") (pinfunction "O_8") (pintype "output"))
    )
    (net (code "153") (name "Net-(E38A-PRE)") (class "Default")
      (node (ref "E38") (pin "4") (pinfunction "PRE_4") (pintype "input"))
      (node (ref "E42") (pin "6") (pinfunction "O_6") (pintype "output"))
    )
    (net (code "154") (name "Net-(E39B-I1)") (class "Default")
      (node (ref "E39") (pin "2") (pinfunction "I1_2") (pintype "input"))
      (node (ref "E45") (pin "10") (pinfunction "O_10") (pintype "output"))
    )
    (net (code "155") (name "Net-(E39B-O)") (class "Default")
      (node (ref "E39") (pin "6") (pinfunction "O_6") (pintype "output"))
      (node (ref "E42") (pin "9") (pinfunction "I_9") (pintype "input"))
    )
    (net (code "156") (name "Net-(E40A-A)") (class "Default")
      (node (ref "E40") (pin "15") (pinfunction "A_15") (pintype "input"))
      (node (ref "E43") (pin "15") (pinfunction "A_15") (pintype "input"))
      (node (ref "E46") (pin "14") (pinfunction "O_14") (pintype "output"))
    )
    (net (code "157") (name "Net-(E40A-B)") (class "Default")
      (node (ref "E40") (pin "14") (pinfunction "B_14") (pintype "input"))
      (node (ref "E43") (pin "14") (pinfunction "B_14") (pintype "input"))
      (node (ref "E46") (pin "3") (pinfunction "O_3") (pintype "output"))
    )
    (net (code "158") (name "Net-(E40A-C)") (class "Default")
      (node (ref "E40") (pin "1") (pinfunction "C_1") (pintype "input"))
      (node (ref "E43") (pin "1") (pinfunction "C_1") (pintype "input"))
      (node (ref "E46") (pin "2") (pinfunction "O_2") (pintype "output"))
    )
    (net (code "159") (name "Net-(E41A-O)") (class "Default")
      (node (ref "E41") (pin "3") (pinfunction "O_3") (pintype "output"))
      (node (ref "E42") (pin "5") (pinfunction "I_5") (pintype "input"))
    )
    (net (code "160") (name "Net-(E42E-I)") (class "Default")
      (node (ref "E42") (pin "11") (pinfunction "I_11") (pintype "input"))
      (node (ref "E45") (pin "4") (pinfunction "O_4") (pintype "output"))
    )
    (net (code "161") (name "Net-(E47A-O)") (class "Default")
      (node (ref "E47") (pin "1") (pinfunction "O_1") (pintype "output"))
      (node (ref "E48") (pin "1") (pinfunction "CLR_1") (pintype "input"))
    )
    (net (code "162") (name "Net-(Q1-B)") (class "Default")
      (node (ref "C58") (pin "1") (pinfunction "1_1") (pintype "passive"))
      (node (ref "C59") (pin "1") (pinfunction "1_1") (pintype "passive"))
      (node (ref "Q1") (pin "2") (pinfunction "B_2") (pintype "passive"))
      (node (ref "R3") (pin "1") (pinfunction "1_1") (pintype "passive"))
    )
    (net (code "163") (name "Net-(Q1-E)") (class "Default")
      (node (ref "C59") (pin "2") (pinfunction "2_2") (pintype "passive"))
      (node (ref "C60") (pin "1") (pinfunction "1_1") (pintype "passive"))
      (node (ref "C61") (pin "1") (pinfunction "1_1") (pintype "passive"))
      (node (ref "Q1") (pin "1") (pinfunction "E_1") (pintype "passive"))
      (node (ref "R4") (pin "1") (pinfunction "1_1") (pintype "passive"))
    )
    (net (code "164") (name "Net-(Q2-E)") (class "Default")
      (node (ref "D4") (pin "A") (pinfunction "A_A") (pintype "passive"))
      (node (ref "Q2") (pin "1") (pinfunction "E_1") (pintype "passive"))
      (node (ref "R8") (pin "1") (pinfunction "1_1") (pintype "passive"))
    )
    (net (code "165") (name "Net-(Q3-B)") (class "Default")
      (node (ref "C63") (pin "1") (pinfunction "1_1") (pintype "passive"))
      (node (ref "Q3") (pin "2") (pinfunction "B_2") (pintype "passive"))
      (node (ref "R13") (pin "2") (pinfunction "2_2") (pintype "passive"))
    )
    (net (code "166") (name "Net-(Q3-C)") (class "Default")
      (node (ref "C63") (pin "2") (pinfunction "2_2") (pintype "passive"))
      (node (ref "D9") (pin "A") (pinfunction "A_A") (pintype "passive"))
      (node (ref "Q3") (pin "3") (pinfunction "C_3") (pintype "passive"))
      (node (ref "R12") (pin "2") (pinfunction "2_2") (pintype "passive"))
    )
    (net (code "167") (name "Net-(R5-Pad2)") (class "Default")
      (node (ref "R5") (pin "2") (pinfunction "2_2") (pintype "passive"))
      (node (ref "R6") (pin "1") (pinfunction "1_1") (pintype "passive"))
      (node (ref "T1") (pin "16") (pinfunction "16_16") (pintype "passive"))
    )
    (net (code "168") (name "Net-(T1-Pad2)") (class "Default")
      (node (ref "T1") (pin "2") (pinfunction "2_2") (pintype "passive"))
      (node (ref "T1") (pin "3") (pinfunction "3_3") (pintype "passive"))
    )
    (net (code "169") (name "Net-(T1-Pad6)") (class "Default")
      (node (ref "T1") (pin "6") (pinfunction "6_6") (pintype "passive"))
      (node (ref "T1") (pin "7") (pinfunction "7_7") (pintype "passive"))
    )
    (net (code "170") (name "Net-(T1-Pad10)") (class "Default")
      (node (ref "T1") (pin "10") (pinfunction "10_10") (pintype "passive"))
      (node (ref "T1") (pin "11") (pinfunction "11_11") (pintype "passive"))
    )
    (net (code "171") (name "Net-(T1-Pad12)") (class "Default")
      (node (ref "T1") (pin "12") (pinfunction "12_12") (pintype "passive"))
      (node (ref "T1") (pin "13") (pinfunction "13_13") (pintype "passive"))
    )
    (net (code "172") (name "Net-(T1-Pad14)") (class "Default")
      (node (ref "T1") (pin "14") (pinfunction "14_14") (pintype "passive"))
      (node (ref "T1") (pin "15") (pinfunction "15_15") (pintype "passive"))
    )
    (net (code "173") (name "POWER_OK") (class "Default")
      (node (ref "E36") (pin "12") (pinfunction "I1_12") (pintype "input"))
      (node (ref "U$2") (pin "BV2") (pinfunction "1_BV2") (pintype "bidirectional"))
    )
    (net (code "174") (name "READER_RUN+") (class "Default")
      (node (ref "C62") (pin "1") (pinfunction "1_1") (pintype "passive"))
      (node (ref "D5") (pin "A") (pinfunction "A_A") (pintype "passive"))
      (node (ref "J1") (pin "PP") (pinfunction "35_PP") (pintype "bidirectional"))
      (node (ref "Q2") (pin "3") (pinfunction "C_3") (pintype "passive"))
    )
    (net (code "175") (name "READER_RUN-") (class "Default")
      (node (ref "J1") (pin "EE") (pinfunction "27_EE") (pintype "bidirectional"))
      (node (ref "R9") (pin "2") (pinfunction "2_2") (pintype "passive"))
    )
    (net (code "176") (name "RTSDTR") (class "Default")
      (node (ref "E32") (pin "6") (pinfunction "O_6") (pintype "output"))
      (node (ref "J1") (pin "DD") (pinfunction "26_DD") (pintype "bidirectional"))
      (node (ref "J1") (pin "V") (pinfunction "18_V") (pintype "bidirectional"))
    )
    (net (code "177") (name "RX20MA_DATA") (class "Default")
      (node (ref "C65") (pin "2") (pinfunction "2_2") (pintype "passive"))
      (node (ref "E36") (pin "2") (pinfunction "O_2") (pintype "output"))
      (node (ref "J1") (pin "H") (pinfunction "7_H") (pintype "bidirectional"))
      (node (ref "R19") (pin "2") (pinfunction "2_2") (pintype "passive"))
    )
    (net (code "178") (name "RX_20MA+") (class "Default")
      (node (ref "C64") (pin "1") (pinfunction "1_1") (pintype "passive"))
      (node (ref "J1") (pin "K") (pinfunction "9_K") (pintype "bidirectional"))
      (node (ref "R16") (pin "1") (pinfunction "1_1") (pintype "passive"))
      (node (ref "R22") (pin "1") (pinfunction "1_1") (pintype "passive"))
      (node (ref "U$2") (pin "BB1") (pinfunction "1_BB1") (pintype "bidirectional"))
    )
    (net (code "179") (name "RX_20MA-") (class "Default")
      (node (ref "C64") (pin "2") (pinfunction "2_2") (pintype "passive"))
      (node (ref "J1") (pin "S") (pinfunction "15_S") (pintype "bidirectional"))
      (node (ref "R17") (pin "2") (pinfunction "2_2") (pintype "passive"))
    )
    (net (code "180") (name "RX_ACTIVE") (class "Default")
      (node (ref "E12") (pin "1") (pinfunction "I0_1") (pintype "input"))
      (node (ref "E7") (pin "11") (pinfunction "CLK_11") (pintype "input"))
      (node (ref "E7") (pin "5") (pinfunction "Q_5") (pintype "output"))
      (node (ref "U$2") (pin "AB1") (pinfunction "1_AB1") (pintype "bidirectional"))
    )
    (net (code "181") (name "RX_BOT") (class "Default")
      (node (ref "E10") (pin "12") (pinfunction "Q4_12") (pintype "output"))
      (node (ref "E48") (pin "2") (pinfunction "D_2") (pintype "input"))
      (node (ref "E8") (pin "2") (pinfunction "D_2") (pintype "input"))
    )
    (net (code "182") (name "RX_DATA") (class "Default")
      (node (ref "E21") (pin "12") (pinfunction "O_12") (pintype "output"))
      (node (ref "J1") (pin "M") (pinfunction "11_M") (pintype "bidirectional"))
    )
    (net (code "183") (name "RX_DIV") (class "Default")
      (node (ref "E12") (pin "9") (pinfunction "I0_9") (pintype "input"))
      (node (ref "E3") (pin "5") (pinfunction "Q_5") (pintype "output"))
    )
    (net (code "184") (name "RX_RATE") (class "Default")
      (node (ref "E18") (pin "1") (pinfunction "CKB_1") (pintype "input"))
      (node (ref "E18") (pin "12") (pinfunction "QA_12") (pintype "output"))
      (node (ref "E19") (pin "13") (pinfunction "I2_13") (pintype "input"))
      (node (ref "E3") (pin "10") (pinfunction "PRE_10") (pintype "input"))
      (node (ref "E3") (pin "3") (pinfunction "CLK_3") (pintype "input"))
      (node (ref "H123") (pin "3") (pinfunction "3_3") (pintype "passive"))
    )
    (net (code "185") (name "RX_SEL_L") (class "Default")
      (node (ref "E42") (pin "12") (pinfunction "O_12") (pintype "output"))
      (node (ref "E43") (pin "2") (pinfunction "D_2") (pintype "input"))
    )
    (net (code "186") (name "SELECTED_L") (class "Default")
      (node (ref "E23") (pin "3") (pinfunction "O_3") (pintype "output"))
      (node (ref "E46") (pin "10") (pinfunction "I1_10") (pintype "input"))
      (node (ref "E46") (pin "5") (pinfunction "I1_5") (pintype "input"))
      (node (ref "E46") (pin "6") (pinfunction "I0_6") (pintype "input"))
    )
    (net (code "187") (name "SERIAL_IN") (class "Default")
      (node (ref "E11") (pin "3") (pinfunction "I1_3") (pintype "input"))
      (node (ref "E19") (pin "1") (pinfunction "I0_1") (pintype "input"))
      (node (ref "E21") (pin "9") (pinfunction "I_9") (pintype "input"))
      (node (ref "J1") (pin "E") (pinfunction "5_E") (pintype "bidirectional"))
    )
    (net (code "188") (name "SKIP_L") (class "Default")
      (node (ref "E37") (pin "10") (pinfunction "O_10") (pintype "open_collector"))
      (node (ref "U$2") (pin "CS1") (pinfunction "1_CS1") (pintype "bidirectional"))
    )
    (net (code "189") (name "STP_MARK") (class "Default")
      (node (ref "E25") (pin "1") (pinfunction "I4_1") (pintype "input"))
      (node (ref "J23") (pin "2") (pinfunction "2_2") (pintype "passive"))
      (node (ref "JJ23") (pin "2") (pinfunction "2_2") (pintype "passive"))
    )
    (net (code "190") (name "TKSKP") (class "Default")
      (node (ref "E39") (pin "4") (pinfunction "I3_4") (pintype "input"))
      (node (ref "E39") (pin "5") (pinfunction "I4_5") (pintype "input"))
      (node (ref "E42") (pin "10") (pinfunction "O_10") (pintype "output"))
    )
    (net (code "191") (name "TP3") (class "Default")
      (node (ref "E34") (pin "9") (pinfunction "I0_9") (pintype "input"))
      (node (ref "U$2") (pin "CH2") (pinfunction "1_CH2") (pintype "bidirectional"))
    )
    (net (code "192") (name "TSKP") (class "Default")
      (node (ref "E45") (pin "13") (pinfunction "O_13") (pintype "output"))
      (node (ref "E45") (pin "6") (pinfunction "I1_6") (pintype "input"))
    )
    (net (code "193") (name "TX_20MA+") (class "Default")
      (node (ref "D6") (pin "C") (pinfunction "C_C") (pintype "passive"))
      (node (ref "D9") (pin "C") (pinfunction "C_C") (pintype "passive"))
      (node (ref "J1") (pin "AA") (pinfunction "23_AA") (pintype "bidirectional"))
      (node (ref "R25") (pin "2") (pinfunction "2_2") (pintype "passive"))
    )
    (net (code "194") (name "TX_20MA-") (class "Default")
      (node (ref "J1") (pin "KK") (pinfunction "31_KK") (pintype "bidirectional"))
      (node (ref "R11") (pin "2") (pinfunction "2_2") (pintype "passive"))
    )
    (net (code "195") (name "TX_ACTIVE") (class "Default")
      (node (ref "E20") (pin "11") (pinfunction "CLK_11") (pintype "input"))
      (node (ref "E20") (pin "6") (pinfunction "~{Q}_6") (pintype "output"))
      (node (ref "E25") (pin "9") (pinfunction "I2_9") (pintype "input"))
      (node (ref "E29") (pin "4") (pinfunction "PRE_4") (pintype "input"))
      (node (ref "E35") (pin "10") (pinfunction "I1_10") (pintype "input"))
      (node (ref "U$2") (pin "BA1") (pinfunction "1_BA1") (pintype "bidirectional"))
    )
    (net (code "196") (name "TX_DATA") (class "Default")
      (node (ref "E29") (pin "2") (pinfunction "D_2") (pintype "input"))
      (node (ref "E31") (pin "11") (pinfunction "Q3_11") (pintype "output"))
    )
    (net (code "197") (name "TX_DIV") (class "Default")
      (node (ref "E16") (pin "5") (pinfunction "Q_5") (pintype "output"))
      (node (ref "E25") (pin "4") (pinfunction "I3_4") (pintype "input"))
      (node (ref "E26") (pin "1") (pinfunction "R_1") (pintype "input"))
      (node (ref "E29") (pin "3") (pinfunction "CLK_3") (pintype "input"))
      (node (ref "E35") (pin "9") (pinfunction "I0_9") (pintype "input"))
      (node (ref "E38") (pin "3") (pinfunction "CLK_3") (pintype "input"))
    )
    (net (code "198") (name "TX_RATE") (class "Default")
      (node (ref "E16") (pin "3") (pinfunction "CLK_3") (pintype "input"))
      (node (ref "E20") (pin "13") (pinfunction "CLR_13") (pintype "input"))
      (node (ref "E20") (pin "3") (pinfunction "CLK_3") (pintype "input"))
      (node (ref "E21") (pin "5") (pinfunction "I_5") (pintype "input"))
      (node (ref "H12") (pin "2") (pinfunction "2_2") (pintype "passive"))
      (node (ref "H123") (pin "2") (pinfunction "2_2") (pintype "passive"))
    )
    (net (code "199") (name "TX_SEL_L") (class "Default")
      (node (ref "E33") (pin "10") (pinfunction "O_10") (pintype "open_collector"))
      (node (ref "E40") (pin "2") (pinfunction "D_2") (pintype "input"))
      (node (ref "R26") (pin "1") (pinfunction "1_1") (pintype "passive"))
    )
    (net (code "200") (name "VCC") (class "Default")
      (node (ref "C1") (pin "1") (pinfunction "1_1") (pintype "passive"))
      (node (ref "C10") (pin "1") (pinfunction "1_1") (pintype "passive"))
      (node (ref "C11") (pin "1") (pinfunction "1_1") (pintype "passive"))
      (node (ref "C12") (pin "1") (pinfunction "1_1") (pintype "passive"))
      (node (ref "C13") (pin "1") (pinfunction "1_1") (pintype "passive"))
      (node (ref "C14") (pin "1") (pinfunction "1_1") (pintype "passive"))
      (node (ref "C15") (pin "1") (pinfunction "1_1") (pintype "passive"))
      (node (ref "C16") (pin "1") (pinfunction "1_1") (pintype "passive"))
      (node (ref "C17") (pin "1") (pinfunction "1_1") (pintype "passive"))
      (node (ref "C18") (pin "1") (pinfunction "1_1") (pintype "passive"))
      (node (ref "C19") (pin "1") (pinfunction "1_1") (pintype "passive"))
      (node (ref "C2") (pin "1") (pinfunction "1_1") (pintype "passive"))
      (node (ref "C20") (pin "1") (pinfunction "1_1") (pintype "passive"))
      (node (ref "C21") (pin "1") (pinfunction "1_1") (pintype "passive"))
      (node (ref "C22") (pin "1") (pinfunction "1_1") (pintype "passive"))
      (node (ref "C23") (pin "1") (pinfunction "1_1") (pintype "passive"))
      (node (ref "C24") (pin "1") (pinfunction "1_1") (pintype "passive"))
      (node (ref "C25") (pin "1") (pinfunction "1_1") (pintype "passive"))
      (node (ref "C26") (pin "1") (pinfunction "1_1") (pintype "passive"))
      (node (ref "C27") (pin "1") (pinfunction "1_1") (pintype "passive"))
      (node (ref "C28") (pin "1") (pinfunction "1_1") (pintype "passive"))
      (node (ref "C29") (pin "1") (pinfunction "1_1") (pintype "passive"))
      (node (ref "C3") (pin "1") (pinfunction "1_1") (pintype "passive"))
      (node (ref "C30") (pin "1") (pinfunction "1_1") (pintype "passive"))
      (node (ref "C31") (pin "1") (pinfunction "1_1") (pintype "passive"))
      (node (ref "C33") (pin "1") (pinfunction "1_1") (pintype "passive"))
      (node (ref "C34") (pin "1") (pinfunction "1_1") (pintype "passive"))
      (node (ref "C35") (pin "1") (pinfunction "1_1") (pintype "passive"))
      (node (ref "C36") (pin "1") (pinfunction "1_1") (pintype "passive"))
      (node (ref "C37") (pin "1") (pinfunction "1_1") (pintype "passive"))
      (node (ref "C38") (pin "1") (pinfunction "1_1") (pintype "passive"))
      (node (ref "C39") (pin "1") (pinfunction "1_1") (pintype "passive"))
      (node (ref "C4") (pin "1") (pinfunction "1_1") (pintype "passive"))
      (node (ref "C40") (pin "1") (pinfunction "1_1") (pintype "passive"))
      (node (ref "C41") (pin "1") (pinfunction "1_1") (pintype "passive"))
      (node (ref "C42") (pin "1") (pinfunction "1_1") (pintype "passive"))
      (node (ref "C43") (pin "1") (pinfunction "1_1") (pintype "passive"))
      (node (ref "C44") (pin "1") (pinfunction "1_1") (pintype "passive"))
      (node (ref "C45") (pin "1") (pinfunction "1_1") (pintype "passive"))
      (node (ref "C46") (pin "1") (pinfunction "1_1") (pintype "passive"))
      (node (ref "C47") (pin "1") (pinfunction "1_1") (pintype "passive"))
      (node (ref "C48") (pin "1") (pinfunction "1_1") (pintype "passive"))
      (node (ref "C5") (pin "1") (pinfunction "1_1") (pintype "passive"))
      (node (ref "C51") (pin "+") (pinfunction "+_+") (pintype "passive"))
      (node (ref "C52") (pin "+") (pinfunction "+_+") (pintype "passive"))
      (node (ref "C53") (pin "+") (pinfunction "+_+") (pintype "passive"))
      (node (ref "C56") (pin "+") (pinfunction "+_+") (pintype "passive"))
      (node (ref "C57") (pin "1") (pinfunction "1_1") (pintype "passive"))
      (node (ref "C6") (pin "1") (pinfunction "1_1") (pintype "passive"))
      (node (ref "C7") (pin "1") (pinfunction "1_1") (pintype "passive"))
      (node (ref "C8") (pin "1") (pinfunction "1_1") (pintype "passive"))
      (node (ref "C9") (pin "1") (pinfunction "1_1") (pintype "passive"))
      (node (ref "D7") (pin "C") (pinfunction "C_C") (pintype "passive"))
      (node (ref "Q1") (pin "3") (pinfunction "C_3") (pintype "passive"))
      (node (ref "Q3") (pin "1") (pinfunction "E_1") (pintype "passive"))
      (node (ref "R1") (pin "2") (pinfunction "2_2") (pintype "passive"))
      (node (ref "R10") (pin "2") (pinfunction "2_2") (pintype "passive"))
      (node (ref "R14") (pin "2") (pinfunction "2_2") (pintype "passive"))
      (node (ref "R15") (pin "2") (pinfunction "2_2") (pintype "passive"))
      (node (ref "R16") (pin "2") (pinfunction "2_2") (pintype "passive"))
      (node (ref "R21") (pin "2") (pinfunction "2_2") (pintype "passive"))
      (node (ref "R24") (pin "2") (pinfunction "2_2") (pintype "passive"))
      (node (ref "R26") (pin "2") (pinfunction "2_2") (pintype "passive"))
      (node (ref "R3") (pin "2") (pinfunction "2_2") (pintype "passive"))
      (node (ref "R7") (pin "2") (pinfunction "2_2") (pintype "passive"))
      (node (ref "R8") (pin "2") (pinfunction "2_2") (pintype "passive"))
      (node (ref "U$2") (pin "AA2") (pinfunction "1_AA2") (pintype "bidirectional"))
      (node (ref "U$2") (pin "BA2") (pinfunction "1_BA2") (pintype "bidirectional"))
      (node (ref "U$2") (pin "CA2") (pinfunction "1_CA2") (pintype "bidirectional"))
    )
    (net (code "201") (name "unconnected-(E3B-Q-Pad9)") (class "Default")
      (node (ref "E3") (pin "9") (pinfunction "Q_9") (pintype "output"))
    )
    (net (code "202") (name "unconnected-(E4A-Q-Pad5)") (class "Default")
      (node (ref "E4") (pin "5") (pinfunction "Q_5") (pintype "output"))
    )
    (net (code "203") (name "unconnected-(E4B-Q-Pad9)") (class "Default")
      (node (ref "E4") (pin "9") (pinfunction "Q_9") (pintype "output"))
    )
    (net (code "204") (name "unconnected-(E5A-QB-Pad9)") (class "Default")
      (node (ref "E5") (pin "9") (pinfunction "QB_9") (pintype "output"))
    )
    (net (code "205") (name "unconnected-(E5A-QC-Pad8)") (class "Default")
      (node (ref "E5") (pin "8") (pinfunction "QC_8") (pintype "output"))
    )
    (net (code "206") (name "unconnected-(E6A-Q4-Pad12)") (class "Default")
      (node (ref "E6") (pin "12") (pinfunction "Q4_12") (pintype "output"))
    )
    (net (code "207") (name "unconnected-(E7B-~{Q}-Pad8)") (class "Default")
      (node (ref "E7") (pin "8") (pinfunction "~{Q}_8") (pintype "output"))
    )
    (net (code "208") (name "unconnected-(E16B-Q-Pad9)") (class "Default")
      (node (ref "E16") (pin "9") (pinfunction "Q_9") (pintype "output"))
    )
    (net (code "209") (name "unconnected-(E18A-QB-Pad9)") (class "Default")
      (node (ref "E18") (pin "9") (pinfunction "QB_9") (pintype "output"))
    )
    (net (code "210") (name "unconnected-(E18A-QC-Pad8)") (class "Default")
      (node (ref "E18") (pin "8") (pinfunction "QC_8") (pintype "output"))
    )
    (net (code "211") (name "unconnected-(E20B-Q-Pad9)") (class "Default")
      (node (ref "E20") (pin "9") (pinfunction "Q_9") (pintype "output"))
    )
    (net (code "212") (name "unconnected-(E22A-BO-Pad13)") (class "Default")
      (node (ref "E22") (pin "13") (pinfunction "BO_13") (pintype "output"))
    )
    (net (code "213") (name "unconnected-(E22A-CO-Pad12)") (class "Default")
      (node (ref "E22") (pin "12") (pinfunction "CO_12") (pintype "output"))
    )
    (net (code "214") (name "unconnected-(E22A-QA-Pad3)") (class "Default")
      (node (ref "E22") (pin "3") (pinfunction "QA_3") (pintype "output"))
    )
    (net (code "215") (name "unconnected-(E22A-QB-Pad2)") (class "Default")
      (node (ref "E22") (pin "2") (pinfunction "QB_2") (pintype "output"))
    )
    (net (code "216") (name "unconnected-(E22A-QC-Pad6)") (class "Default")
      (node (ref "E22") (pin "6") (pinfunction "QC_6") (pintype "output"))
    )
    (net (code "217") (name "unconnected-(E25A-I5-Pad12)") (class "Default")
      (node (ref "E25") (pin "12") (pinfunction "I5_12") (pintype "passive"))
    )
    (net (code "218") (name "unconnected-(E25A-I6-Pad11)") (class "Default")
      (node (ref "E25") (pin "11") (pinfunction "I6_11") (pintype "passive"))
    )
    (net (code "219") (name "unconnected-(E26A-I0-Pad3)") (class "Default")
      (node (ref "E26") (pin "3") (pinfunction "I0_3") (pintype "input"))
    )
    (net (code "220") (name "unconnected-(E26A-I1-Pad2)") (class "Default")
      (node (ref "E26") (pin "2") (pinfunction "I1_2") (pintype "input"))
    )
    (net (code "221") (name "unconnected-(E26A-I2-Pad15)") (class "Default")
      (node (ref "E26") (pin "15") (pinfunction "I2_15") (pintype "input"))
    )
    (net (code "222") (name "unconnected-(E26A-I3-Pad14)") (class "Default")
      (node (ref "E26") (pin "14") (pinfunction "I3_14") (pintype "input"))
    )
    (net (code "223") (name "unconnected-(E26A-Q1-Pad7)") (class "Default")
      (node (ref "E26") (pin "7") (pinfunction "Q1_7") (pintype "output"))
    )
    (net (code "224") (name "unconnected-(E26A-Q3-Pad11)") (class "Default")
      (node (ref "E26") (pin "11") (pinfunction "Q3_11") (pintype "output"))
    )
    (net (code "225") (name "unconnected-(E26A-Q4-Pad12)") (class "Default")
      (node (ref "E26") (pin "12") (pinfunction "Q4_12") (pintype "output"))
    )
    (net (code "226") (name "unconnected-(E28A-Q4-Pad12)") (class "Default")
      (node (ref "E28") (pin "12") (pinfunction "Q4_12") (pintype "output"))
    )
    (net (code "227") (name "unconnected-(E29B-~{Q}-Pad8)") (class "Default")
      (node (ref "E29") (pin "8") (pinfunction "~{Q}_8") (pintype "output"))
    )
    (net (code "228") (name "unconnected-(E31A-Q4-Pad12)") (class "Default")
      (node (ref "E31") (pin "12") (pinfunction "Q4_12") (pintype "output"))
    )
    (net (code "229") (name "unconnected-(E38A-~{Q}-Pad6)") (class "Default")
      (node (ref "E38") (pin "6") (pinfunction "~{Q}_6") (pintype "output"))
    )
    (net (code "230") (name "unconnected-(E39A-I5-Pad12)") (class "Default")
      (node (ref "E39") (pin "12") (pinfunction "I5_12") (pintype "passive"))
    )
    (net (code "231") (name "unconnected-(E39A-I6-Pad11)") (class "Default")
      (node (ref "E39") (pin "11") (pinfunction "I6_11") (pintype "passive"))
    )
    (net (code "232") (name "unconnected-(E40A-3-Pad10)") (class "Default")
      (node (ref "E40") (pin "10") (pinfunction "3_10") (pintype "output"))
    )
    (net (code "233") (name "unconnected-(E40A-7-Pad5)") (class "Default")
      (node (ref "E40") (pin "5") (pinfunction "7_5") (pintype "output"))
    )
    (net (code "234") (name "unconnected-(E40A-8-Pad6)") (class "Default")
      (node (ref "E40") (pin "6") (pinfunction "8_6") (pintype "output"))
    )
    (net (code "235") (name "unconnected-(E40A-9-Pad7)") (class "Default")
      (node (ref "E40") (pin "7") (pinfunction "9_7") (pintype "output"))
    )
    (net (code "236") (name "unconnected-(E43A-3-Pad10)") (class "Default")
      (node (ref "E43") (pin "10") (pinfunction "3_10") (pintype "output"))
    )
    (net (code "237") (name "unconnected-(E43A-7-Pad5)") (class "Default")
      (node (ref "E43") (pin "5") (pinfunction "7_5") (pintype "output"))
    )
    (net (code "238") (name "unconnected-(E43A-8-Pad6)") (class "Default")
      (node (ref "E43") (pin "6") (pinfunction "8_6") (pintype "output"))
    )
    (net (code "239") (name "unconnected-(E43A-9-Pad7)") (class "Default")
      (node (ref "E43") (pin "7") (pinfunction "9_7") (pintype "output"))
    )
    (net (code "240") (name "unconnected-(E48A-Q-Pad5)") (class "Default")
      (node (ref "E48") (pin "5") (pinfunction "Q_5") (pintype "output"))
    )
    (net (code "241") (name "unconnected-(E48B-~{Q}-Pad8)") (class "Default")
      (node (ref "E48") (pin "8") (pinfunction "~{Q}_8") (pintype "output"))
    )
    (net (code "242") (name "unconnected-(J1-4-PadD)") (class "Default")
      (node (ref "J1") (pin "D") (pinfunction "4_D") (pintype "bidirectional"))
    )
    (net (code "243") (name "unconnected-(J1-10-PadL)") (class "Default")
      (node (ref "J1") (pin "L") (pinfunction "10_L") (pintype "bidirectional"))
    )
    (net (code "244") (name "unconnected-(J1-12-PadN)") (class "Default")
      (node (ref "J1") (pin "N") (pinfunction "12_N") (pintype "bidirectional"))
    )
    (net (code "245") (name "unconnected-(J1-13-PadP)") (class "Default")
      (node (ref "J1") (pin "P") (pinfunction "13_P") (pintype "bidirectional"))
    )
    (net (code "246") (name "unconnected-(J1-14-PadR)") (class "Default")
      (node (ref "J1") (pin "R") (pinfunction "14_R") (pintype "bidirectional"))
    )
    (net (code "247") (name "unconnected-(J1-16-PadT)") (class "Default")
      (node (ref "J1") (pin "T") (pinfunction "16_T") (pintype "bidirectional"))
    )
    (net (code "248") (name "unconnected-(J1-17-PadU)") (class "Default")
      (node (ref "J1") (pin "U") (pinfunction "17_U") (pintype "bidirectional"))
    )
    (net (code "249") (name "unconnected-(J1-19-PadW)") (class "Default")
      (node (ref "J1") (pin "W") (pinfunction "19_W") (pintype "bidirectional"))
    )
    (net (code "250") (name "unconnected-(J1-20-PadX)") (class "Default")
      (node (ref "J1") (pin "X") (pinfunction "20_X") (pintype "bidirectional"))
    )
    (net (code "251") (name "unconnected-(J1-21-PadY)") (class "Default")
      (node (ref "J1") (pin "Y") (pinfunction "21_Y") (pintype "bidirectional"))
    )
    (net (code "252") (name "unconnected-(J1-22-PadZ)") (class "Default")
      (node (ref "J1") (pin "Z") (pinfunction "22_Z") (pintype "bidirectional"))
    )
    (net (code "253") (name "unconnected-(J1-24-PadBB)") (class "Default")
      (node (ref "J1") (pin "BB") (pinfunction "24_BB") (pintype "bidirectional"))
    )
    (net (code "254") (name "unconnected-(J1-25-PadCC)") (class "Default")
      (node (ref "J1") (pin "CC") (pinfunction "25_CC") (pintype "bidirectional"))
    )
    (net (code "255") (name "unconnected-(J1-28-PadFF)") (class "Default")
      (node (ref "J1") (pin "FF") (pinfunction "28_FF") (pintype "bidirectional"))
    )
    (net (code "256") (name "unconnected-(J1-29-PadHH)") (class "Default")
      (node (ref "J1") (pin "HH") (pinfunction "29_HH") (pintype "bidirectional"))
    )
    (net (code "257") (name "unconnected-(J1-30-PadJJ)") (class "Default")
      (node (ref "J1") (pin "JJ") (pinfunction "30_JJ") (pintype "bidirectional"))
    )
    (net (code "258") (name "unconnected-(J1-32-PadLL)") (class "Default")
      (node (ref "J1") (pin "LL") (pinfunction "32_LL") (pintype "bidirectional"))
    )
    (net (code "259") (name "unconnected-(J1-33-PadMM)") (class "Default")
      (node (ref "J1") (pin "MM") (pinfunction "33_MM") (pintype "bidirectional"))
    )
    (net (code "260") (name "unconnected-(J1-34-PadNN)") (class "Default")
      (node (ref "J1") (pin "NN") (pinfunction "34_NN") (pintype "bidirectional"))
    )
    (net (code "261") (name "unconnected-(J1-36-PadRR)") (class "Default")
      (node (ref "J1") (pin "RR") (pinfunction "36_RR") (pintype "bidirectional"))
    )
    (net (code "262") (name "unconnected-(J1-37-PadSS)") (class "Default")
      (node (ref "J1") (pin "SS") (pinfunction "37_SS") (pintype "bidirectional"))
    )
    (net (code "263") (name "unconnected-(J1-38-PadTT)") (class "Default")
      (node (ref "J1") (pin "TT") (pinfunction "38_TT") (pintype "bidirectional"))
    )
    (net (code "264") (name "~{CKKCC}") (class "Default")
      (node (ref "E35") (pin "4") (pinfunction "I0_4") (pintype "input"))
      (node (ref "E44") (pin "11") (pinfunction "O_11") (pintype "output"))
      (node (ref "E48") (pin "13") (pinfunction "CLR_13") (pintype "input"))
    )
    (net (code "265") (name "~{CKTFL}") (class "Default")
      (node (ref "E38") (pin "1") (pinfunction "CLR_1") (pintype "input"))
      (node (ref "E42") (pin "2") (pinfunction "O_2") (pintype "output"))
    )
    (net (code "266") (name "~{DOTPC}") (class "Default")
      (node (ref "E27") (pin "10") (pinfunction "I1_10") (pintype "input"))
      (node (ref "E27") (pin "11") (pinfunction "I0_11") (pintype "input"))
      (node (ref "E27") (pin "5") (pinfunction "I1_5") (pintype "input"))
      (node (ref "E27") (pin "6") (pinfunction "I0_6") (pintype "input"))
      (node (ref "E28") (pin "13") (pinfunction "S_13") (pintype "input"))
      (node (ref "E30") (pin "10") (pinfunction "I1_10") (pintype "input"))
      (node (ref "E30") (pin "11") (pinfunction "I0_11") (pintype "input"))
      (node (ref "E30") (pin "5") (pinfunction "I1_5") (pintype "input"))
      (node (ref "E30") (pin "6") (pinfunction "I0_6") (pintype "input"))
      (node (ref "E31") (pin "13") (pinfunction "S_13") (pintype "input"))
      (node (ref "E35") (pin "3") (pinfunction "O_3") (pintype "output"))
      (node (ref "R10") (pin "1") (pinfunction "1_1") (pintype "passive"))
    )
    (net (code "267") (name "~{INIT}") (class "Default")
      (node (ref "E16") (pin "13") (pinfunction "CLR_13") (pintype "input"))
      (node (ref "E16") (pin "4") (pinfunction "PRE_4") (pintype "input"))
      (node (ref "E29") (pin "13") (pinfunction "CLR_13") (pintype "input"))
      (node (ref "E46") (pin "13") (pinfunction "O_13") (pintype "output"))
      (node (ref "E48") (pin "10") (pinfunction "PRE_10") (pintype "input"))
    )
    (net (code "268") (name "~{INT_ENAB}") (class "Default")
      (node (ref "E38") (pin "9") (pinfunction "Q_9") (pintype "output"))
      (node (ref "E45") (pin "9") (pinfunction "I1_9") (pintype "input"))
    )
    (net (code "269") (name "~{KCC}") (class "Default")
      (node (ref "E43") (pin "11") (pinfunction "2_11") (pintype "output"))
      (node (ref "E44") (pin "10") (pinfunction "I1_10") (pintype "input"))
    )
    (net (code "270") (name "~{KCF}") (class "Default")
      (node (ref "E43") (pin "13") (pinfunction "0_13") (pintype "output"))
      (node (ref "E47") (pin "6") (pinfunction "I1_6") (pintype "input"))
    )
    (net (code "271") (name "~{KIE}") (class "Default")
      (node (ref "E43") (pin "3") (pinfunction "5_3") (pintype "output"))
      (node (ref "E47") (pin "8") (pinfunction "I0_8") (pintype "input"))
    )
    (net (code "272") (name "~{KRB}") (class "Default")
      (node (ref "E43") (pin "4") (pinfunction "6_4") (pintype "output"))
      (node (ref "E44") (pin "4") (pinfunction "I0_4") (pintype "input"))
      (node (ref "E44") (pin "9") (pinfunction "I0_9") (pintype "input"))
    )
    (net (code "273") (name "~{KRS}") (class "Default")
      (node (ref "E43") (pin "9") (pinfunction "4_9") (pintype "output"))
      (node (ref "E44") (pin "5") (pinfunction "I1_5") (pintype "input"))
    )
    (net (code "274") (name "~{KSF}") (class "Default")
      (node (ref "E43") (pin "12") (pinfunction "1_12") (pintype "output"))
      (node (ref "E47") (pin "11") (pinfunction "I0_11") (pintype "input"))
    )
    (net (code "275") (name "~{LAST_UNIT}") (class "Default")
      (node (ref "E12") (pin "12") (pinfunction "I0_12") (pintype "input"))
      (node (ref "E8") (pin "6") (pinfunction "~{Q}_6") (pintype "output"))
    )
    (net (code "276") (name "~{LINE}") (class "Default")
      (node (ref "E29") (pin "6") (pinfunction "~{Q}_6") (pintype "output"))
      (node (ref "R13") (pin "1") (pinfunction "1_1") (pintype "passive"))
      (node (ref "R14") (pin "1") (pinfunction "1_1") (pintype "passive"))
    )
    (net (code "277") (name "~{P_PULSE}") (class "Default")
      (node (ref "E10") (pin "13") (pinfunction "S_13") (pintype "input"))
      (node (ref "E11") (pin "8") (pinfunction "I0_8") (pintype "input"))
      (node (ref "E6") (pin "13") (pinfunction "S_13") (pintype "input"))
      (node (ref "E7") (pin "9") (pinfunction "Q_9") (pintype "output"))
    )
    (net (code "278") (name "~{RFLG}") (class "Default")
      (node (ref "E44") (pin "1") (pinfunction "I0_1") (pintype "input"))
      (node (ref "E47") (pin "12") (pinfunction "I1_12") (pintype "input"))
      (node (ref "E48") (pin "6") (pinfunction "~{Q}_6") (pintype "output"))
    )
    (net (code "279") (name "~{RX_ACTIVE}") (class "Default")
      (node (ref "E12") (pin "13") (pinfunction "I1_13") (pintype "input"))
      (node (ref "E12") (pin "4") (pinfunction "I0_4") (pintype "input"))
      (node (ref "E7") (pin "6") (pinfunction "~{Q}_6") (pintype "output"))
    )
    (net (code "280") (name "~{RX_DIV}") (class "Default")
      (node (ref "E3") (pin "6") (pinfunction "~{Q}_6") (pintype "output"))
      (node (ref "E4") (pin "3") (pinfunction "CLK_3") (pintype "input"))
    )
    (net (code "281") (name "~{R_RUN}") (class "Default")
      (node (ref "E48") (pin "9") (pinfunction "Q_9") (pintype "output"))
      (node (ref "Q2") (pin "2") (pinfunction "B_2") (pintype "passive"))
      (node (ref "U$2") (pin "DB1") (pinfunction "1_DB1") (pintype "bidirectional"))
    )
    (net (code "282") (name "~{SPIKE_DET}") (class "Default")
      (node (ref "E11") (pin "2") (pinfunction "I0_2") (pintype "input"))
      (node (ref "E16") (pin "8") (pinfunction "~{Q}_8") (pintype "output"))
    )
    (net (code "283") (name "~{START}") (class "Default")
      (node (ref "E20") (pin "8") (pinfunction "~{Q}_8") (pintype "output"))
      (node (ref "E29") (pin "1") (pinfunction "CLR_1") (pintype "input"))
    )
    (net (code "284") (name "~{TCF}") (class "Default")
      (node (ref "E40") (pin "11") (pinfunction "2_11") (pintype "output"))
      (node (ref "E41") (pin "10") (pinfunction "I1_10") (pintype "input"))
    )
    (net (code "285") (name "~{TFLG}") (class "Default")
      (node (ref "E38") (pin "5") (pinfunction "Q_5") (pintype "output"))
      (node (ref "E44") (pin "2") (pinfunction "I1_2") (pintype "input"))
      (node (ref "E45") (pin "11") (pinfunction "I0_11") (pintype "input"))
    )
    (net (code "286") (name "~{TFL}") (class "Default")
      (node (ref "E40") (pin "13") (pinfunction "0_13") (pintype "output"))
      (node (ref "E45") (pin "2") (pinfunction "I0_2") (pintype "input"))
    )
    (net (code "287") (name "~{TLS}") (class "Default")
      (node (ref "E40") (pin "4") (pinfunction "6_4") (pintype "output"))
      (node (ref "E41") (pin "4") (pinfunction "I0_4") (pintype "input"))
      (node (ref "E41") (pin "9") (pinfunction "I0_9") (pintype "input"))
    )
    (net (code "288") (name "~{TP3}") (class "Default")
      (node (ref "E42") (pin "4") (pinfunction "O_4") (pintype "output"))
      (node (ref "E45") (pin "3") (pinfunction "I1_3") (pintype "input"))
      (node (ref "E47") (pin "5") (pinfunction "I0_5") (pintype "input"))
      (node (ref "E47") (pin "9") (pinfunction "I1_9") (pintype "input"))
    )
    (net (code "289") (name "~{TPC}") (class "Default")
      (node (ref "E40") (pin "9") (pinfunction "4_9") (pintype "output"))
      (node (ref "E41") (pin "5") (pinfunction "I1_5") (pintype "input"))
    )
    (net (code "290") (name "~{TSF}") (class "Default")
      (node (ref "E40") (pin "12") (pinfunction "1_12") (pintype "output"))
      (node (ref "E45") (pin "12") (pinfunction "I1_12") (pintype "input"))
    )
    (net (code "291") (name "~{TSK}") (class "Default")
      (node (ref "E40") (pin "3") (pinfunction "5_3") (pintype "output"))
      (node (ref "E45") (pin "8") (pinfunction "I0_8") (pintype "input"))
    )
    (net (code "292") (name "~{TX_ACTIVE}") (class "Default")
      (node (ref "E20") (pin "5") (pinfunction "Q_5") (pintype "output"))
      (node (ref "E26") (pin "4") (pinfunction "D_4") (pintype "input"))
    )
    (net (code "293") (name "~{TX_DIV}") (class "Default")
      (node (ref "DL1") (pin "1") (pinfunction "1_1") (pintype "passive"))
      (node (ref "E16") (pin "6") (pinfunction "~{Q}_6") (pintype "output"))
      (node (ref "E19") (pin "4") (pinfunction "I1_4") (pintype "input"))
      (node (ref "R21") (pin "1") (pinfunction "1_1") (pintype "passive"))
    )
  )
)
